# EK-TM4C1294XL_REV_D.net
KiCad netlist of a schematic drawn in EAGLE
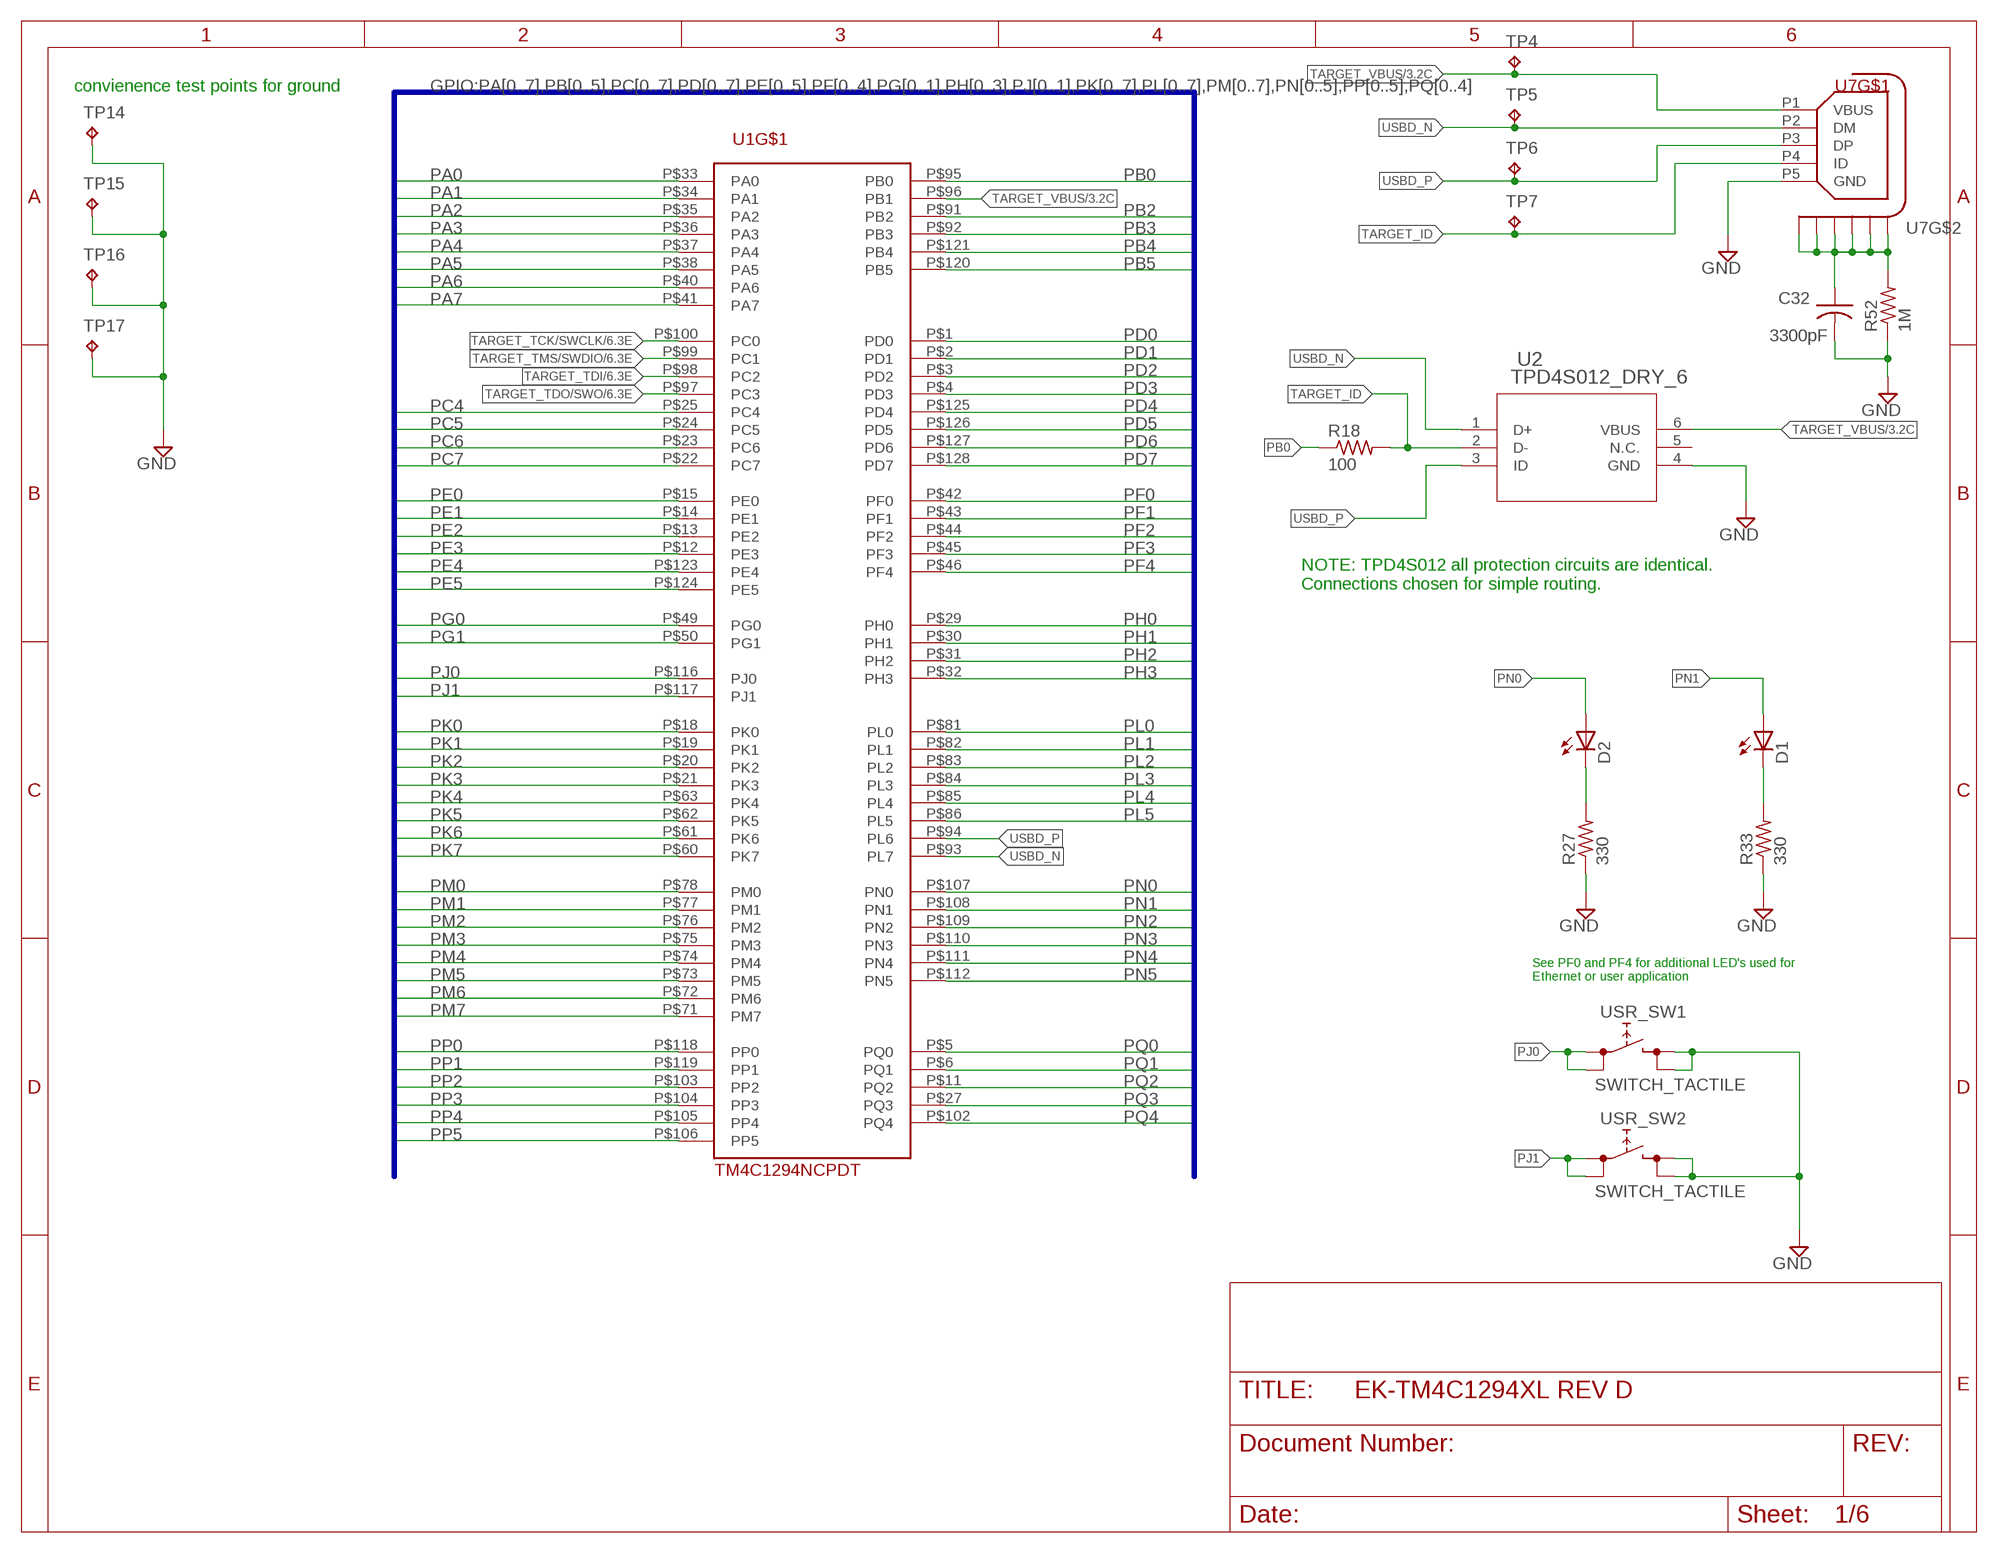
[diagram p0: schematic, sheet 1]
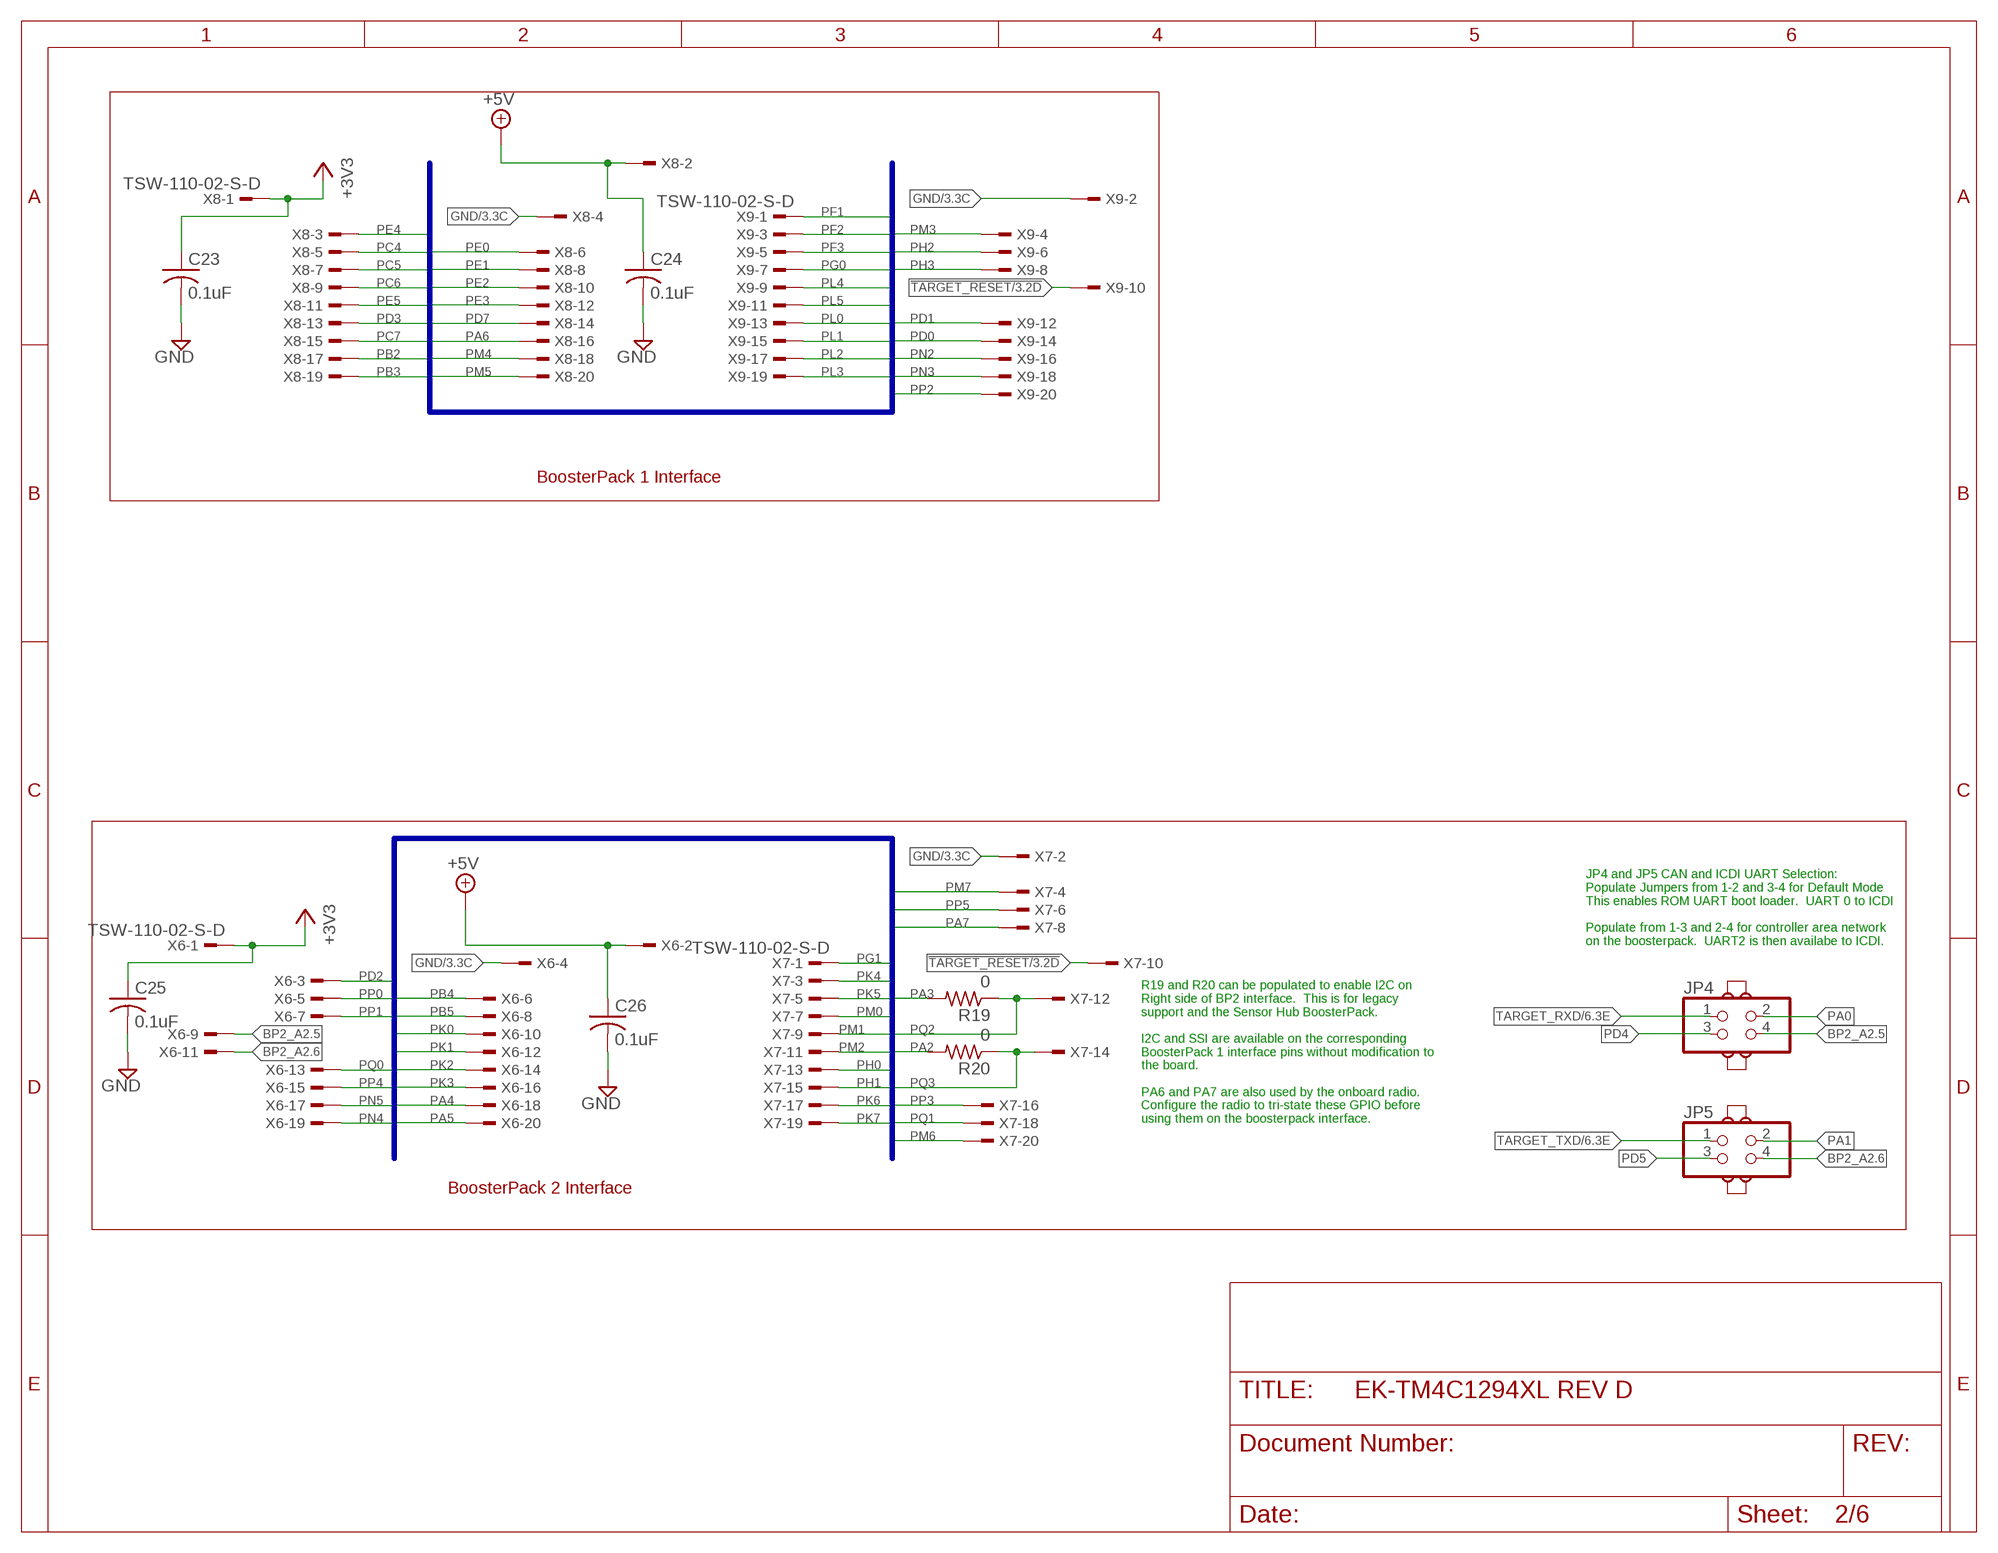
[diagram p1: schematic, sheet 2]
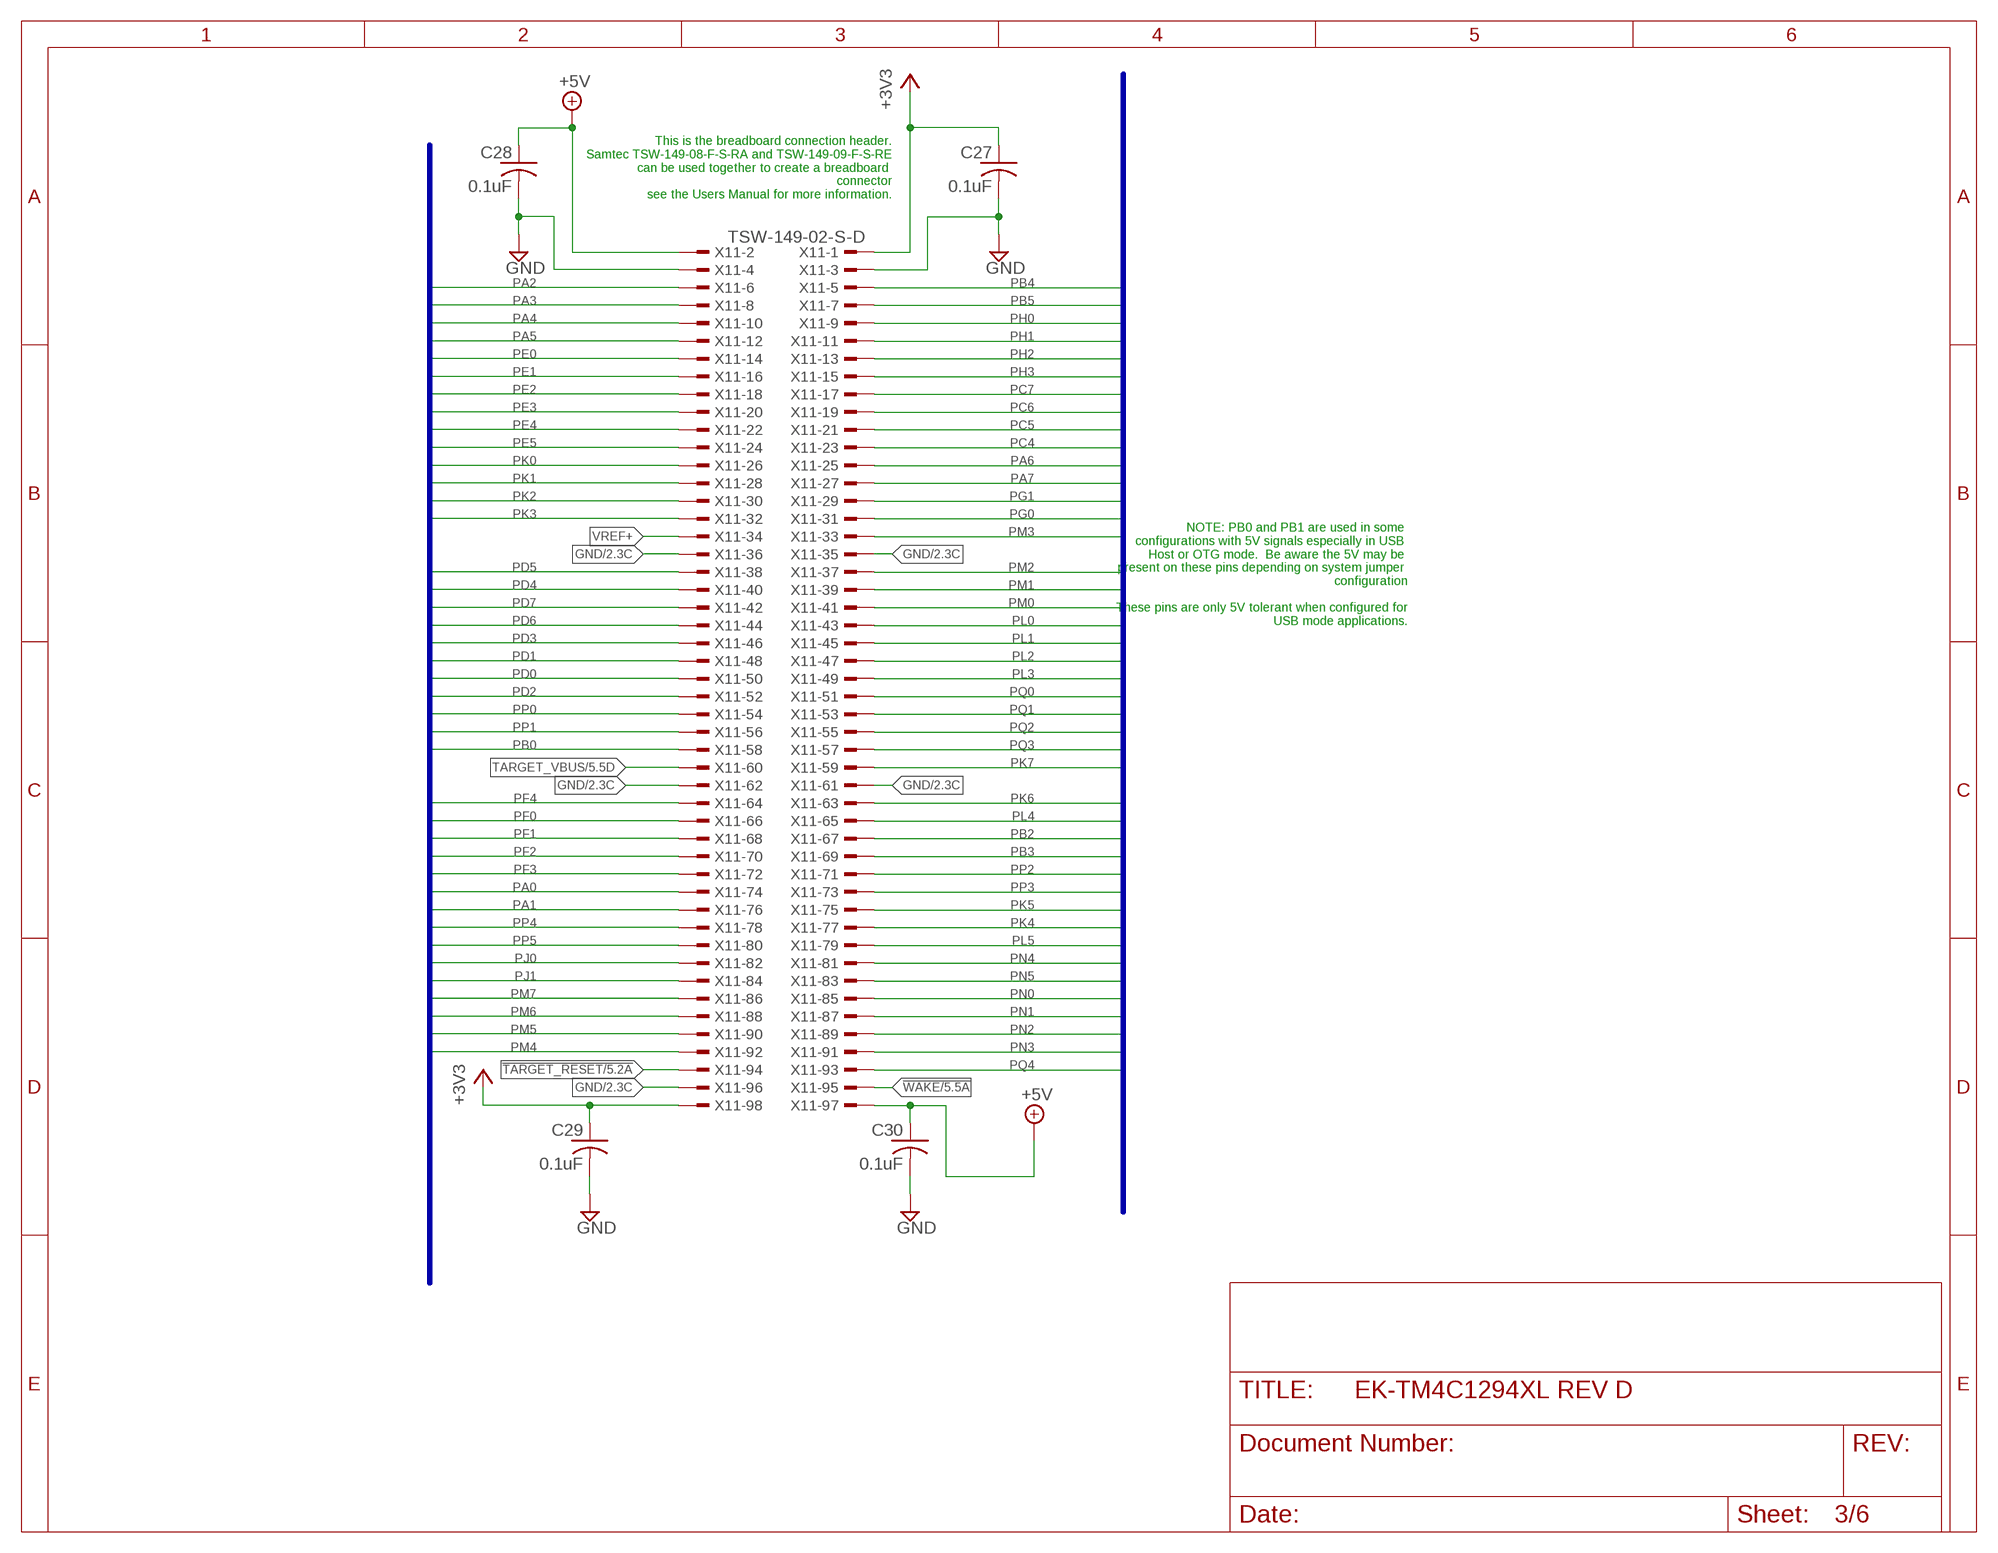
[diagram p2: schematic, sheet 3]
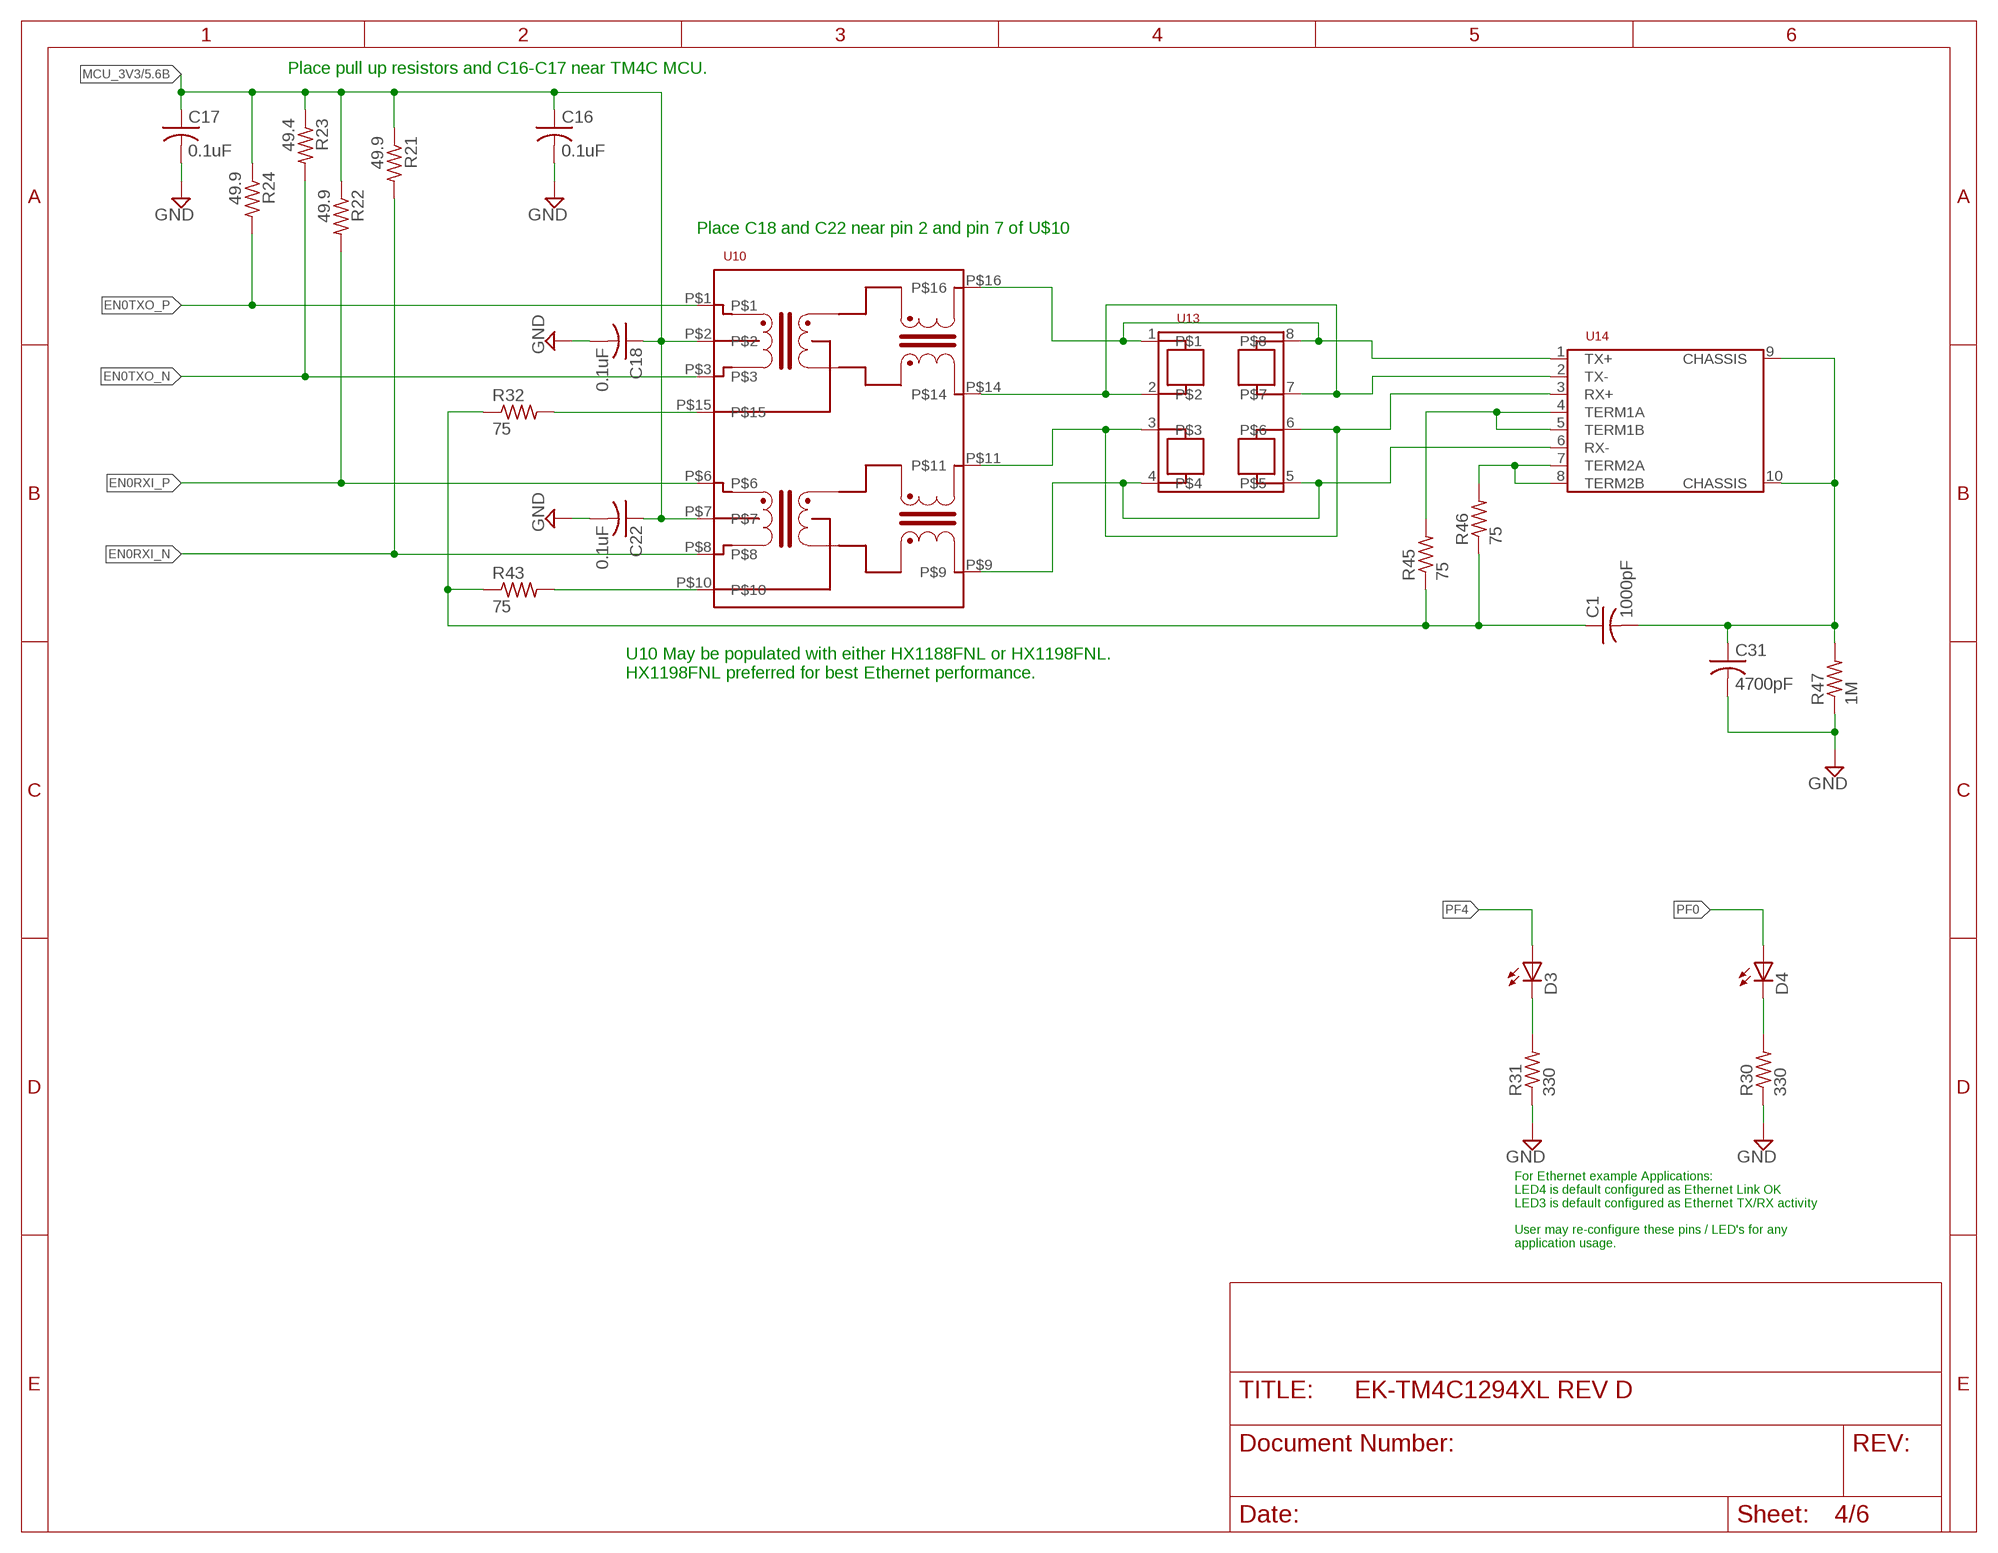
[diagram p3: schematic, sheet 4]
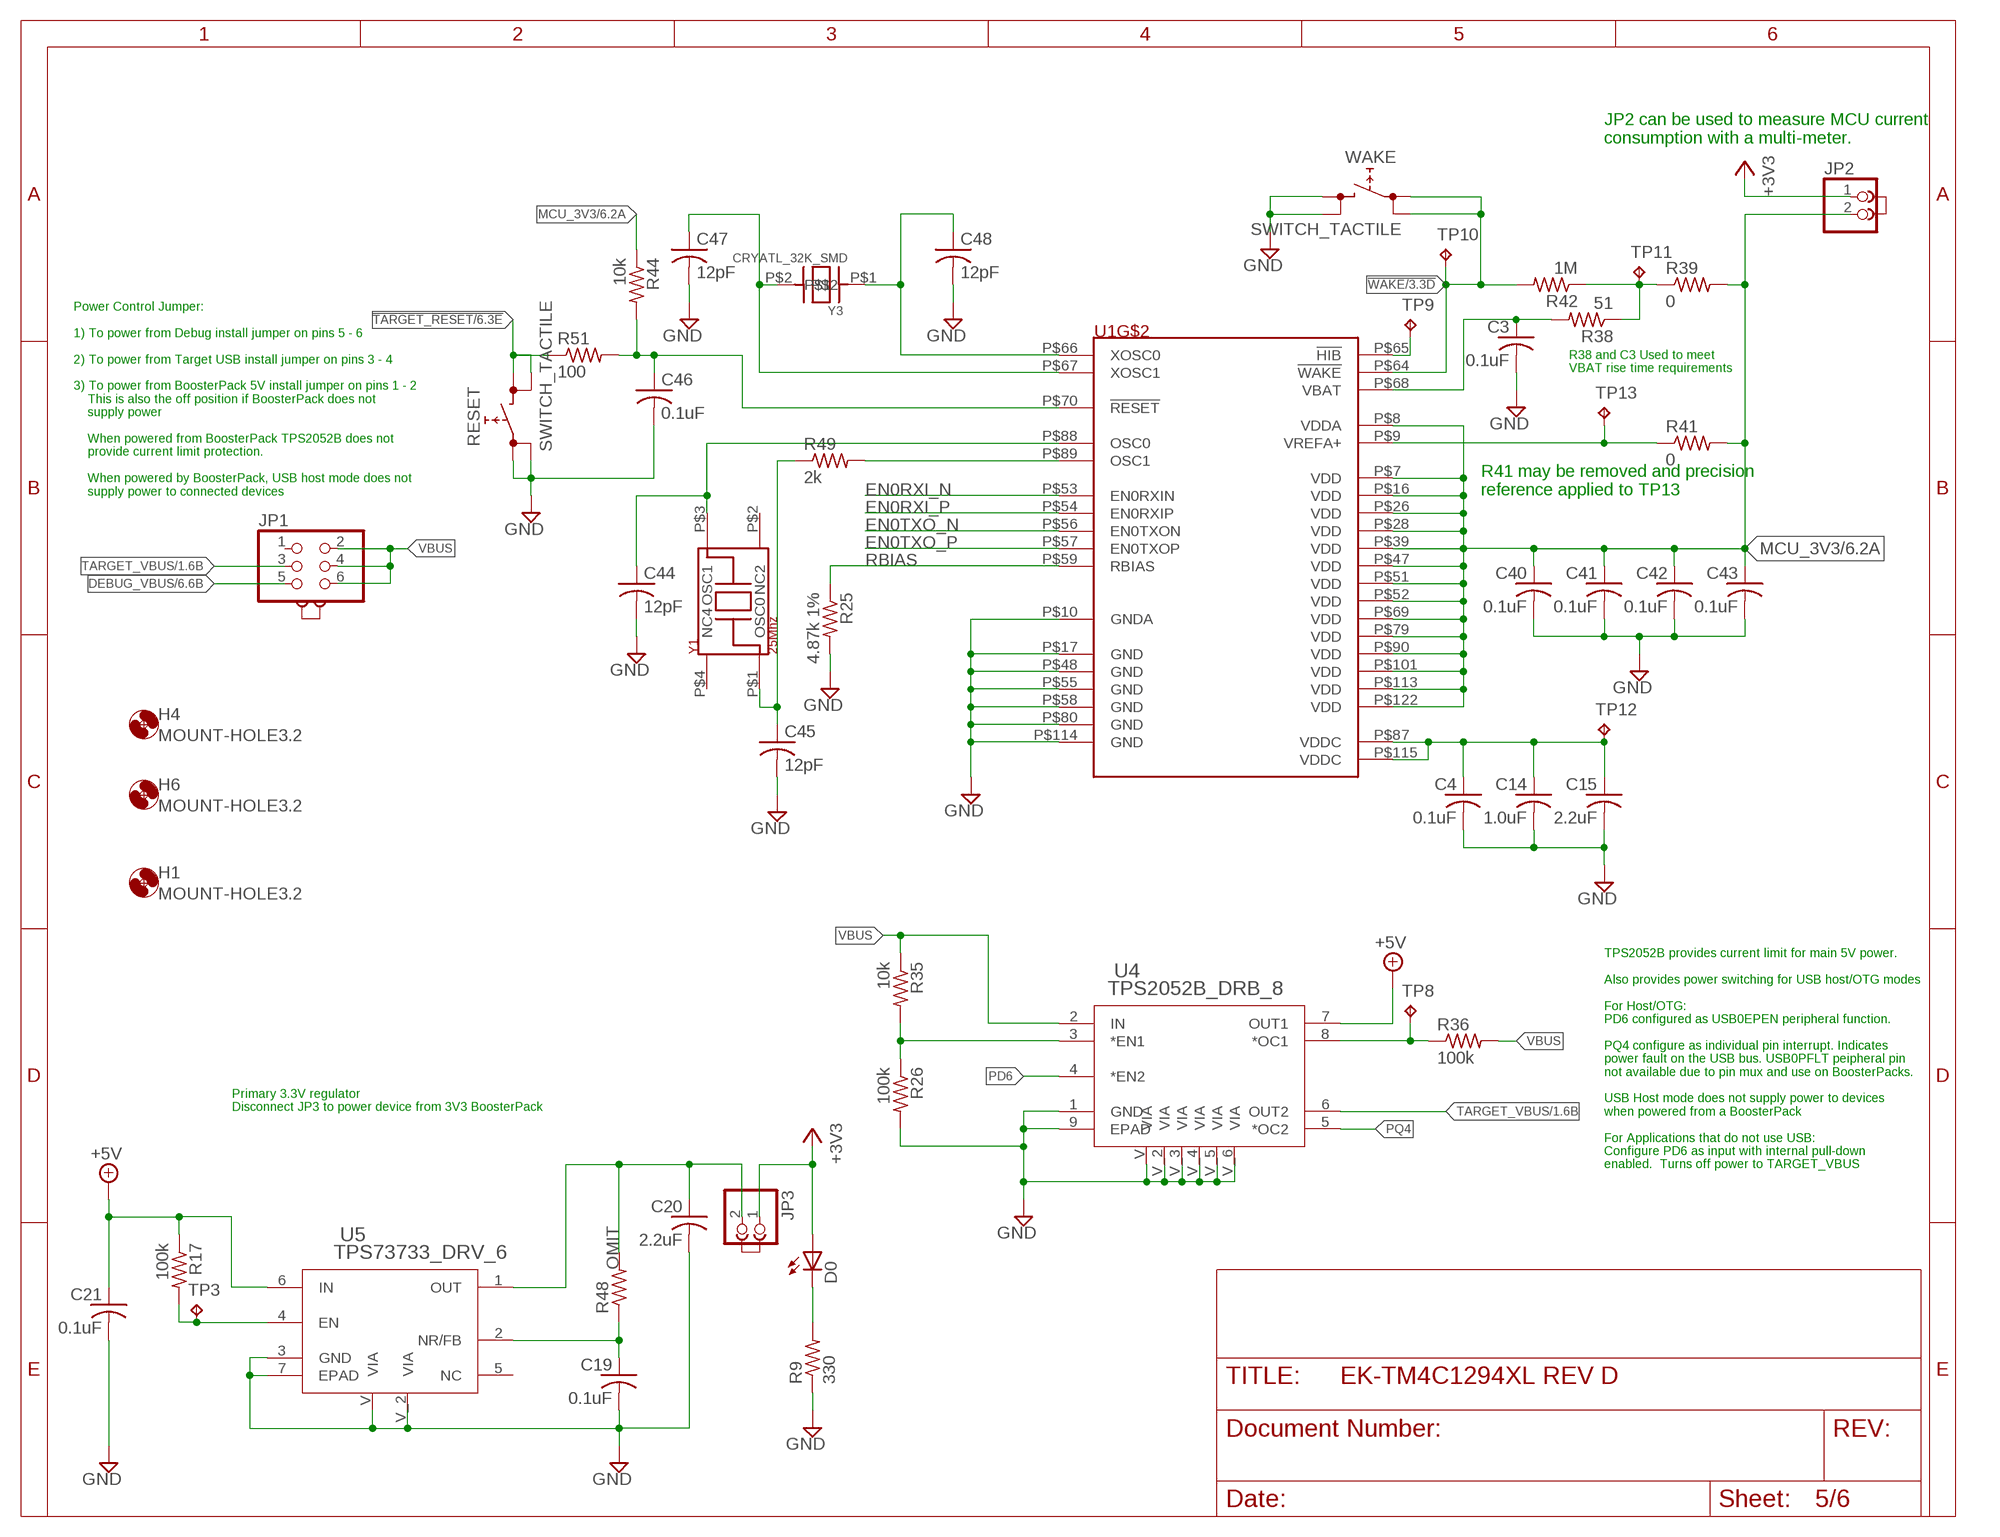
[diagram p4: schematic, sheet 5]
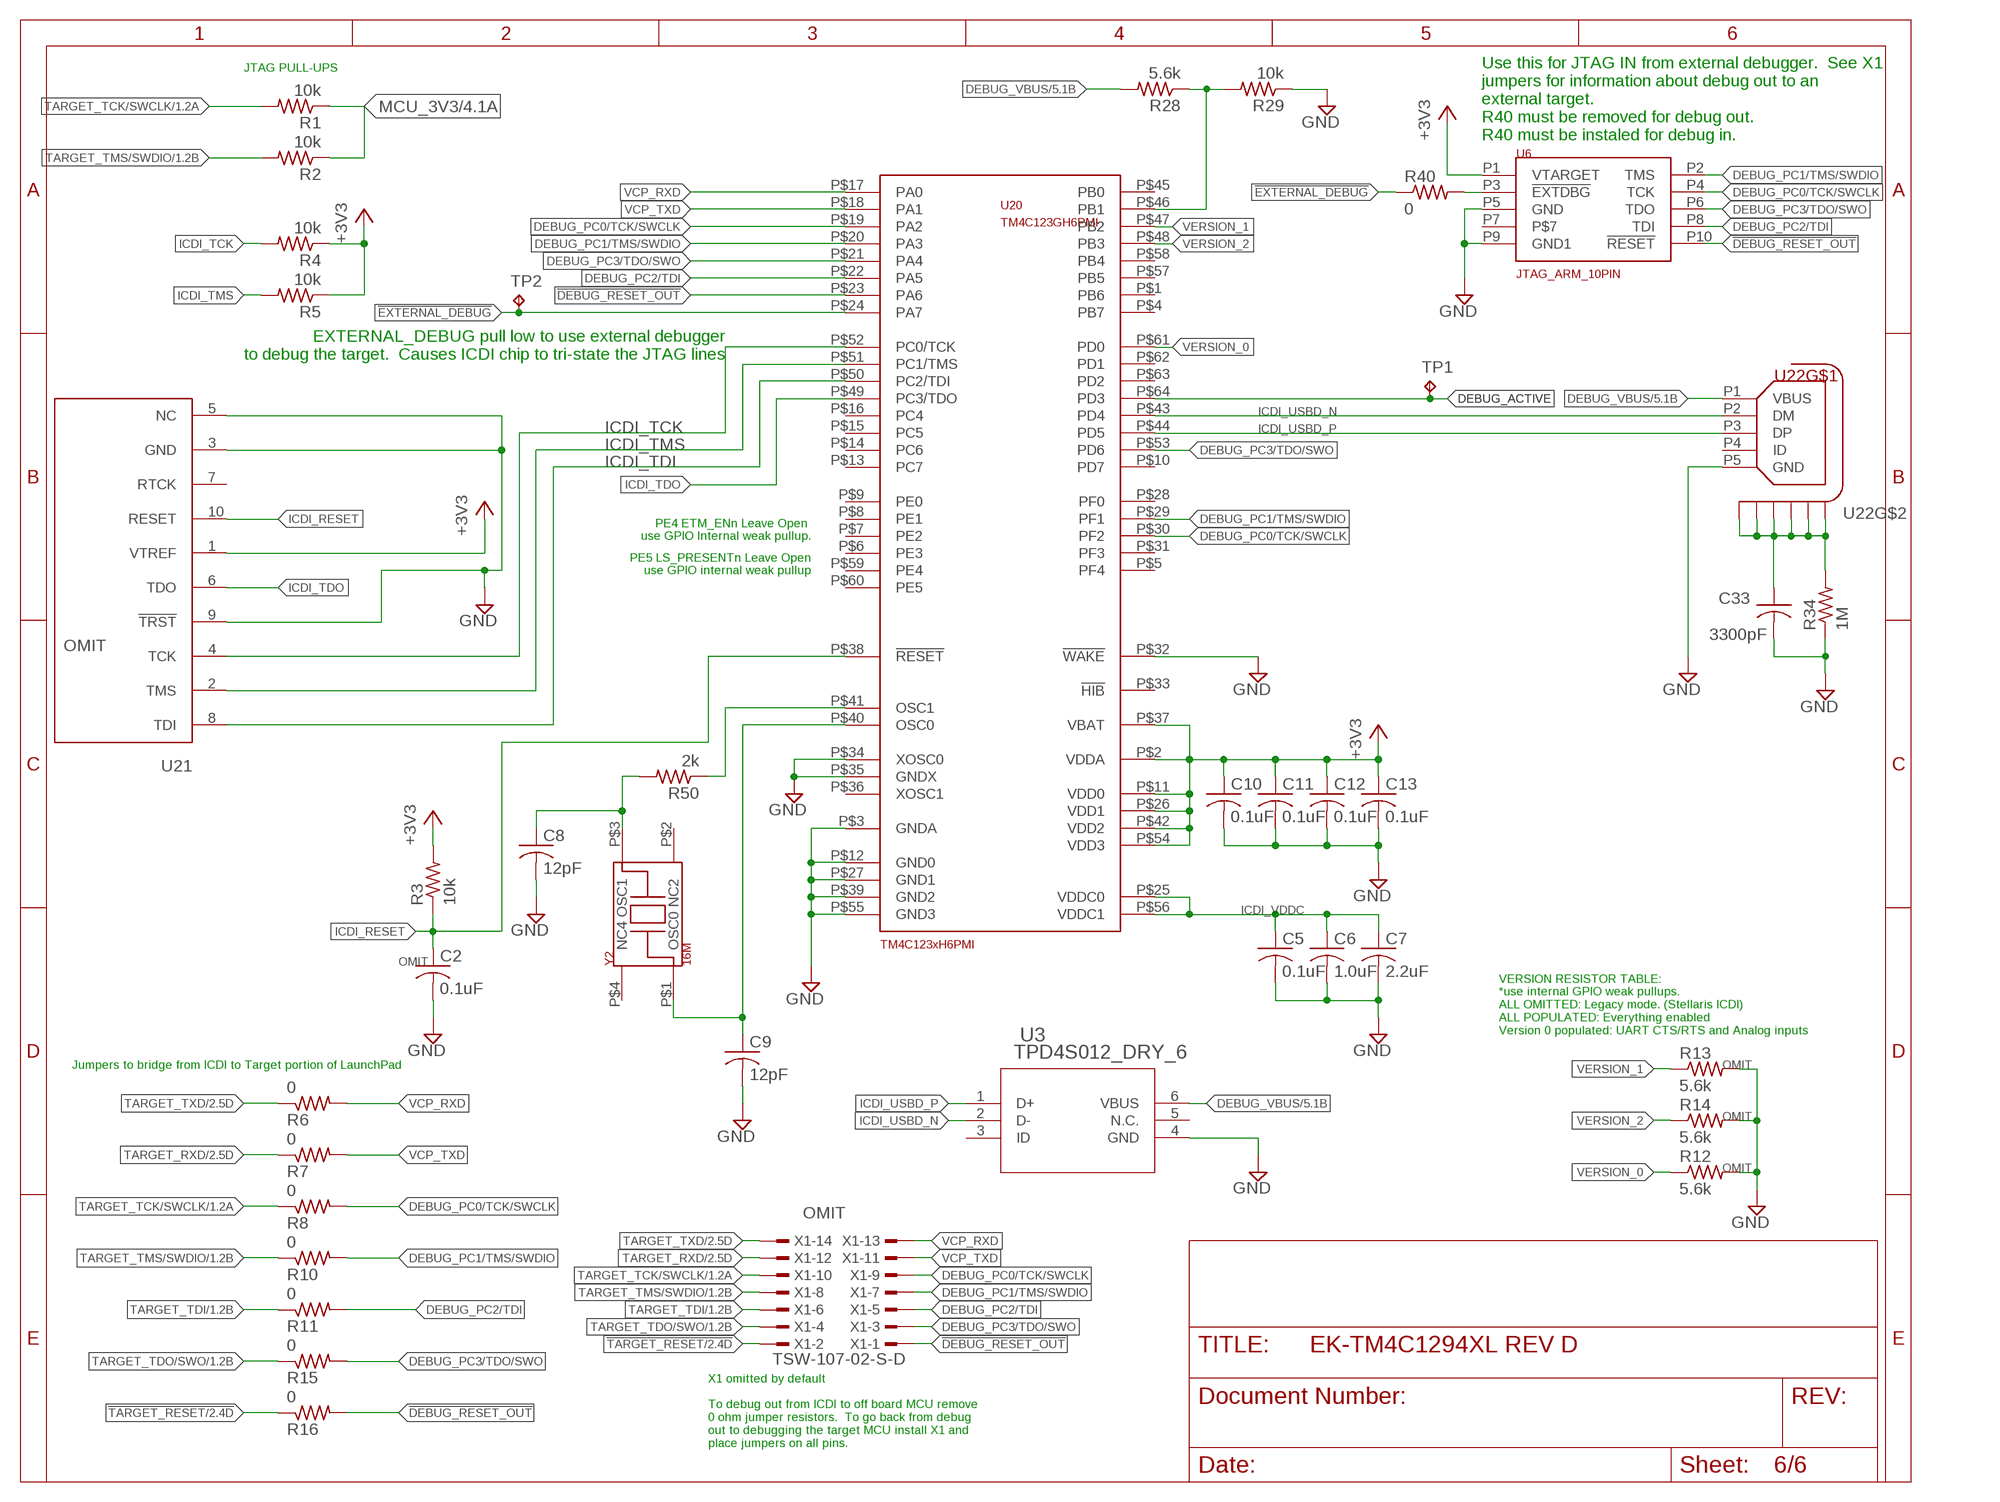
[diagram p5: schematic, sheet 6]

(export (version "E")
  (design (tool "Eeschema 10.0.6"))
  (components
    (comp (ref "C2")
      (value "0.1uF")
      (footprint "eagle-import:C0402")
      (fields (field (name "POPOP") "OMIT"))
      (libsource (lib "eagle-import") (part "ek-tm4c129exl_C-USC0402"))
    )
    (comp (ref "C5")
      (value "0.1uF")
      (footprint "eagle-import:C0402")
      (libsource (lib "eagle-import") (part "ek-tm4c129exl_C-USC0402"))
    )
    (comp (ref "C6")
      (value "1.0uF")
      (footprint "eagle-import:C0402")
      (libsource (lib "eagle-import") (part "ek-tm4c129exl_C-USC0402"))
    )
    (comp (ref "C7")
      (value "2.2uF")
      (footprint "eagle-import:C0603")
      (libsource (lib "eagle-import") (part "ek-tm4c129exl_C-USC0603"))
    )
    (comp (ref "C8")
      (value "12pF")
      (footprint "eagle-import:C0402")
      (libsource (lib "eagle-import") (part "ek-tm4c129exl_C-USC0402"))
    )
    (comp (ref "C9")
      (value "12pF")
      (footprint "eagle-import:C0402")
      (libsource (lib "eagle-import") (part "ek-tm4c129exl_C-USC0402"))
    )
    (comp (ref "C10")
      (value "0.1uF")
      (footprint "eagle-import:C0402")
      (libsource (lib "eagle-import") (part "ek-tm4c129exl_C-USC0402"))
    )
    (comp (ref "C11")
      (value "0.1uF")
      (footprint "eagle-import:C0402")
      (libsource (lib "eagle-import") (part "ek-tm4c129exl_C-USC0402"))
    )
    (comp (ref "C12")
      (value "0.1uF")
      (footprint "eagle-import:C0402")
      (libsource (lib "eagle-import") (part "ek-tm4c129exl_C-USC0402"))
    )
    (comp (ref "C13")
      (value "0.1uF")
      (footprint "eagle-import:C0402")
      (libsource (lib "eagle-import") (part "ek-tm4c129exl_C-USC0402"))
    )
    (comp (ref "C33")
      (value "3300pF")
      (footprint "eagle-import:C0603")
      (libsource (lib "eagle-import") (part "C-USC0603"))
    )
    (comp (ref "R1")
      (value "10k")
      (footprint "eagle-import:R0402")
      (libsource (lib "eagle-import") (part "ek-tm4c129exl_R-US_R0402"))
    )
    (comp (ref "R2")
      (value "10k")
      (footprint "eagle-import:R0402")
      (libsource (lib "eagle-import") (part "ek-tm4c129exl_R-US_R0402"))
    )
    (comp (ref "R3")
      (value "10k")
      (footprint "eagle-import:R0402")
      (libsource (lib "eagle-import") (part "ek-tm4c129exl_R-US_R0402"))
    )
    (comp (ref "R4")
      (value "10k")
      (footprint "eagle-import:R0402")
      (libsource (lib "eagle-import") (part "ek-tm4c129exl_R-US_R0402"))
    )
    (comp (ref "R5")
      (value "10k")
      (footprint "eagle-import:R0402")
      (libsource (lib "eagle-import") (part "ek-tm4c129exl_R-US_R0402"))
    )
    (comp (ref "R6")
      (value "0")
      (footprint "eagle-import:R0402")
      (libsource (lib "eagle-import") (part "ek-tm4c129exl_R-US_R0402"))
    )
    (comp (ref "R7")
      (value "0")
      (footprint "eagle-import:R0402")
      (libsource (lib "eagle-import") (part "ek-tm4c129exl_R-US_R0402"))
    )
    (comp (ref "R8")
      (value "0")
      (footprint "eagle-import:R0402")
      (libsource (lib "eagle-import") (part "ek-tm4c129exl_R-US_R0402"))
    )
    (comp (ref "R10")
      (value "0")
      (footprint "eagle-import:R0402")
      (libsource (lib "eagle-import") (part "ek-tm4c129exl_R-US_R0402"))
    )
    (comp (ref "R11")
      (value "0")
      (footprint "eagle-import:R0402")
      (libsource (lib "eagle-import") (part "ek-tm4c129exl_R-US_R0402"))
    )
    (comp (ref "R12")
      (value "5.6k")
      (footprint "eagle-import:R0402")
      (fields (field (name "POPOP") "OMIT"))
      (libsource (lib "eagle-import") (part "ek-tm4c129exl_R-US_R0402"))
    )
    (comp (ref "R13")
      (value "5.6k")
      (footprint "eagle-import:R0402")
      (fields (field (name "POPOP") "OMIT"))
      (libsource (lib "eagle-import") (part "ek-tm4c129exl_R-US_R0402"))
    )
    (comp (ref "R14")
      (value "5.6k")
      (footprint "eagle-import:R0402")
      (fields (field (name "POPOP") "OMIT"))
      (libsource (lib "eagle-import") (part "ek-tm4c129exl_R-US_R0402"))
    )
    (comp (ref "R15")
      (value "0")
      (footprint "eagle-import:R0402")
      (libsource (lib "eagle-import") (part "ek-tm4c129exl_R-US_R0402"))
    )
    (comp (ref "R16")
      (value "0")
      (footprint "eagle-import:R0402")
      (libsource (lib "eagle-import") (part "ek-tm4c129exl_R-US_R0402"))
    )
    (comp (ref "R28")
      (value "5.6k")
      (footprint "eagle-import:R0402")
      (libsource (lib "eagle-import") (part "ek-tm4c129exl_R-US_R0402"))
    )
    (comp (ref "R29")
      (value "10k")
      (footprint "eagle-import:R0402")
      (libsource (lib "eagle-import") (part "ek-tm4c129exl_R-US_R0402"))
    )
    (comp (ref "R34")
      (value "1M")
      (footprint "eagle-import:R0603")
      (libsource (lib "eagle-import") (part "R-US_R0603"))
    )
    (comp (ref "R40")
      (value "0")
      (footprint "eagle-import:R0402")
      (libsource (lib "eagle-import") (part "ek-tm4c129exl_R-US_R0402"))
    )
    (comp (ref "R50")
      (value "2k")
      (footprint "eagle-import:R0402")
      (libsource (lib "eagle-import") (part "ek-tm4c129exl_R-US_R0402"))
    )
    (comp (ref "TP1")
      (value "TPPAD1-13")
      (footprint "eagle-import:P1-13")
      (libsource (lib "eagle-import") (part "TPPAD1-13"))
    )
    (comp (ref "TP2")
      (value "TPPAD1-13")
      (footprint "eagle-import:P1-13")
      (libsource (lib "eagle-import") (part "TPPAD1-13"))
    )
    (comp (ref "U3")
      (value "TPD4S012_DRY_6")
      (footprint "eagle-import:DRY6")
      (fields
        (field (name "GENERIC_PART_NUMBER") "TPD4S012")
        (field (name "MANUFACTURER") "Texas Instruments")
        (field (name "MANUFACTURER_PART_NUMBER") "tpd4s012_dry_6")
      )
      (libsource (lib "eagle-import") (part "TPD4S012_DRY_6"))
    )
    (comp (ref "U6")
      (value "JTAG_ARM_10PIN")
      (footprint "eagle-import:CON_2X5_50MIL")
      (libsource (lib "eagle-import") (part "JTAG_ARM_10PIN"))
    )
    (comp (ref "U20")
      (value "TM4C123GH6PMI")
      (footprint "eagle-import:LQFP-64-PM")
      (libsource (lib "eagle-import") (part "TM4C123GH6PMI"))
    )
    (comp (ref "U21")
      (value "TC2050-NL-MCP-NL")
      (footprint "eagle-import:TC2030-MCP-NL")
      (fields (field (name "POPOP") "OMIT"))
      (libsource (lib "eagle-import") (part "TC2050-NL-MCP-NL"))
    )
    (comp (ref "U22")
      (value "CON_USB_FCI_MICRO_B_10118194")
      (footprint "eagle-import:CON_USB_MICRO_B_FCI_10118194")
      (fields (field (name "GNUM") "G20-USBU-THB-CEB"))
      (libsource (lib "eagle-import") (part "CON_USB_FCI_MICRO_B_10118194"))
    )
    (comp (ref "X1")
      (value "TSW-107-02-S-D")
      (footprint "eagle-import:TSW-107-02-S-D")
      (fields (field (name "GNUM") "G22-THVEU-2X7P-BAB") (field (name "POPOP") "OMIT"))
      (libsource (lib "eagle-import") (part "TSW-107-02-S-D"))
    )
    (comp (ref "Y2")
      (value "16M")
      (footprint "eagle-import:NDK3.2X2.5")
      (libsource (lib "eagle-import") (part "NX3225GA"))
    )
    (comp (ref "C32")
      (value "3300pF")
      (footprint "eagle-import:C0603")
      (libsource (lib "eagle-import") (part "C-USC0603"))
    )
    (comp (ref "D1")
      (value "LEDCHIPLED_0603")
      (footprint "eagle-import:CHIPLED_0603")
      (libsource (lib "eagle-import") (part "LEDCHIPLED_0603"))
    )
    (comp (ref "D2")
      (value "LEDCHIPLED_0603")
      (footprint "eagle-import:CHIPLED_0603")
      (libsource (lib "eagle-import") (part "LEDCHIPLED_0603"))
    )
    (comp (ref "R18")
      (value "100")
      (footprint "eagle-import:R0402")
      (libsource (lib "eagle-import") (part "ek-tm4c129exl_R-US_R0402"))
    )
    (comp (ref "R27")
      (value "330")
      (footprint "eagle-import:R0402")
      (libsource (lib "eagle-import") (part "ek-tm4c129exl_R-US_R0402"))
    )
    (comp (ref "R33")
      (value "330")
      (footprint "eagle-import:R0402")
      (libsource (lib "eagle-import") (part "ek-tm4c129exl_R-US_R0402"))
    )
    (comp (ref "R52")
      (value "1M")
      (footprint "eagle-import:R0603")
      (libsource (lib "eagle-import") (part "R-US_R0603"))
    )
    (comp (ref "TP4")
      (value "TPPAD1-13")
      (footprint "eagle-import:P1-13")
      (libsource (lib "eagle-import") (part "TPPAD1-13"))
    )
    (comp (ref "TP5")
      (value "TPPAD1-13")
      (footprint "eagle-import:P1-13")
      (libsource (lib "eagle-import") (part "TPPAD1-13"))
    )
    (comp (ref "TP6")
      (value "TPPAD1-13")
      (footprint "eagle-import:P1-13")
      (libsource (lib "eagle-import") (part "TPPAD1-13"))
    )
    (comp (ref "TP7")
      (value "TPPAD1-13")
      (footprint "eagle-import:P1-13")
      (libsource (lib "eagle-import") (part "TPPAD1-13"))
    )
    (comp (ref "TP14")
      (value "TPPAD1-13")
      (footprint "eagle-import:P1-13")
      (libsource (lib "eagle-import") (part "TPPAD1-13"))
    )
    (comp (ref "TP15")
      (value "TPPAD1-13")
      (footprint "eagle-import:P1-13")
      (libsource (lib "eagle-import") (part "TPPAD1-13"))
    )
    (comp (ref "TP16")
      (value "TPPAD1-13")
      (footprint "eagle-import:P1-13")
      (libsource (lib "eagle-import") (part "TPPAD1-13"))
    )
    (comp (ref "TP17")
      (value "TPPAD1-13")
      (footprint "eagle-import:P1-13")
      (libsource (lib "eagle-import") (part "TPPAD1-13"))
    )
    (comp (ref "U1")
      (value "TM4C1294NCPDT")
      (footprint "eagle-import:TQFP-128")
      (fields (field (name "GNUM") "G50-QF128-C1294-ALH"))
      (libsource (lib "eagle-import") (part "TM4C1294NCPDT"))
    )
    (comp (ref "U2")
      (value "TPD4S012_DRY_6")
      (footprint "eagle-import:DRY6")
      (fields
        (field (name "GENERIC_PART_NUMBER") "TPD4S012")
        (field (name "MANUFACTURER") "Texas Instruments")
        (field (name "MANUFACTURER_PART_NUMBER") "tpd4s012_dry_6")
      )
      (libsource (lib "eagle-import") (part "TPD4S012_DRY_6"))
    )
    (comp (ref "U7")
      (value "CON_USB_HIROSE_MICRO_AB_ZX62D_AB_5P8")
      (footprint "eagle-import:CON_USB_MICRO_AB_HIROSE_ZX62D-AB-5P8")
      (fields (field (name "GNUM") "G20-USBU-THAB-CEB"))
      (libsource (lib "eagle-import") (part "CON_USB_HIROSE_MICRO_AB_ZX62D_AB_5P8"))
    )
    (comp (ref "USR_SW1")
      (value "SWITCH_TACTILE")
      (footprint "eagle-import:SWITCH_6MM_6MM_TE_CON_SMD")
      (libsource (lib "eagle-import") (part "SWITCH_TACTILE"))
    )
    (comp (ref "USR_SW2")
      (value "SWITCH_TACTILE")
      (footprint "eagle-import:SWITCH_6MM_6MM_TE_CON_SMD")
      (libsource (lib "eagle-import") (part "SWITCH_TACTILE"))
    )
    (comp (ref "C3")
      (value "0.1uF")
      (footprint "eagle-import:C0402")
      (libsource (lib "eagle-import") (part "ek-tm4c129exl_C-USC0402"))
    )
    (comp (ref "C4")
      (value "0.1uF")
      (footprint "eagle-import:C0402")
      (libsource (lib "eagle-import") (part "ek-tm4c129exl_C-USC0402"))
    )
    (comp (ref "C14")
      (value "1.0uF")
      (footprint "eagle-import:C0402")
      (libsource (lib "eagle-import") (part "ek-tm4c129exl_C-USC0402"))
    )
    (comp (ref "C15")
      (value "2.2uF")
      (footprint "eagle-import:C0603K")
      (fields (field (name "DIGIKEY_PARTNUM") "311-1451-2-ND"))
      (libsource (lib "eagle-import") (part "ek-tm4c129exl_C-USC0603K"))
    )
    (comp (ref "C19")
      (value "0.1uF")
      (footprint "eagle-import:C0402")
      (libsource (lib "eagle-import") (part "ek-tm4c129exl_C-USC0402"))
    )
    (comp (ref "C20")
      (value "2.2uF")
      (footprint "eagle-import:C0603K")
      (fields (field (name "DIGIKEY_PARTNUM") "311-1451-2-ND"))
      (libsource (lib "eagle-import") (part "ek-tm4c129exl_C-USC0603K"))
    )
    (comp (ref "C21")
      (value "0.1uF")
      (footprint "eagle-import:C0402")
      (libsource (lib "eagle-import") (part "ek-tm4c129exl_C-USC0402"))
    )
    (comp (ref "C40")
      (value "0.1uF")
      (footprint "eagle-import:C0402")
      (libsource (lib "eagle-import") (part "ek-tm4c129exl_C-USC0402"))
    )
    (comp (ref "C41")
      (value "0.1uF")
      (footprint "eagle-import:C0402")
      (libsource (lib "eagle-import") (part "ek-tm4c129exl_C-USC0402"))
    )
    (comp (ref "C42")
      (value "0.1uF")
      (footprint "eagle-import:C0402")
      (libsource (lib "eagle-import") (part "ek-tm4c129exl_C-USC0402"))
    )
    (comp (ref "C43")
      (value "0.1uF")
      (footprint "eagle-import:C0402")
      (libsource (lib "eagle-import") (part "ek-tm4c129exl_C-USC0402"))
    )
    (comp (ref "C44")
      (value "12pF")
      (footprint "eagle-import:C0402")
      (libsource (lib "eagle-import") (part "ek-tm4c129exl_C-USC0402"))
    )
    (comp (ref "C45")
      (value "12pF")
      (footprint "eagle-import:C0402")
      (libsource (lib "eagle-import") (part "ek-tm4c129exl_C-USC0402"))
    )
    (comp (ref "C46")
      (value "0.1uF")
      (footprint "eagle-import:C0402")
      (libsource (lib "eagle-import") (part "ek-tm4c129exl_C-USC0402"))
    )
    (comp (ref "C47")
      (value "12pF")
      (footprint "eagle-import:C0402")
      (libsource (lib "eagle-import") (part "ek-tm4c129exl_C-USC0402"))
    )
    (comp (ref "C48")
      (value "12pF")
      (footprint "eagle-import:C0402")
      (libsource (lib "eagle-import") (part "ek-tm4c129exl_C-USC0402"))
    )
    (comp (ref "D0")
      (value "LEDCHIPLED_0603")
      (footprint "eagle-import:CHIPLED_0603")
      (libsource (lib "eagle-import") (part "LEDCHIPLED_0603"))
    )
    (comp (ref "H1")
      (value "MOUNT-HOLE3.2")
      (footprint "eagle-import:3,2")
      (libsource (lib "eagle-import") (part "MOUNT-HOLE3.2"))
    )
    (comp (ref "H4")
      (value "MOUNT-HOLE3.2")
      (footprint "eagle-import:3,2")
      (libsource (lib "eagle-import") (part "MOUNT-HOLE3.2"))
    )
    (comp (ref "H6")
      (value "MOUNT-HOLE3.2")
      (footprint "eagle-import:3,2")
      (libsource (lib "eagle-import") (part "MOUNT-HOLE3.2"))
    )
    (comp (ref "J1")
      (value "JUMPER")
      (footprint "eagle-import:JUMP")
      (libsource (lib "eagle-import") (part "JUMPER"))
    )
    (comp (ref "J2")
      (value "JUMPER")
      (footprint "eagle-import:JUMP")
      (libsource (lib "eagle-import") (part "JUMPER"))
    )
    (comp (ref "J3")
      (value "JUMPER")
      (footprint "eagle-import:JUMP")
      (libsource (lib "eagle-import") (part "JUMPER"))
    )
    (comp (ref "JP1")
      (value "PINHD-2X3")
      (footprint "eagle-import:2X03")
      (libsource (lib "eagle-import") (part "PINHD-2X3"))
    )
    (comp (ref "JP2")
      (value "PINHD-1X2")
      (footprint "eagle-import:1X02")
      (libsource (lib "eagle-import") (part "PINHD-1X2"))
    )
    (comp (ref "JP3")
      (value "PINHD-1X2")
      (footprint "eagle-import:1X02")
      (libsource (lib "eagle-import") (part "PINHD-1X2"))
    )
    (comp (ref "R9")
      (value "330")
      (footprint "eagle-import:R0402")
      (libsource (lib "eagle-import") (part "ek-tm4c129exl_R-US_R0402"))
    )
    (comp (ref "R17")
      (value "100k")
      (footprint "eagle-import:R0402")
      (libsource (lib "eagle-import") (part "ek-tm4c129exl_R-US_R0402"))
    )
    (comp (ref "R25")
      (value "4.87k 1%")
      (footprint "eagle-import:R0402")
      (libsource (lib "eagle-import") (part "ek-tm4c129exl_R-US_R0402"))
    )
    (comp (ref "R26")
      (value "100k")
      (footprint "eagle-import:R0402")
      (libsource (lib "eagle-import") (part "ek-tm4c129exl_R-US_R0402"))
    )
    (comp (ref "R35")
      (value "10k")
      (footprint "eagle-import:R0402")
      (libsource (lib "eagle-import") (part "ek-tm4c129exl_R-US_R0402"))
    )
    (comp (ref "R36")
      (value "100k")
      (footprint "eagle-import:R0402")
      (libsource (lib "eagle-import") (part "ek-tm4c129exl_R-US_R0402"))
    )
    (comp (ref "R38")
      (value "51")
      (footprint "eagle-import:R0402")
      (libsource (lib "eagle-import") (part "ek-tm4c129exl_R-US_R0402"))
    )
    (comp (ref "R39")
      (value "0")
      (footprint "eagle-import:R0402")
      (libsource (lib "eagle-import") (part "ek-tm4c129exl_R-US_R0402"))
    )
    (comp (ref "R41")
      (value "0")
      (footprint "eagle-import:R0402")
      (libsource (lib "eagle-import") (part "ek-tm4c129exl_R-US_R0402"))
    )
    (comp (ref "R42")
      (value "1M")
      (footprint "eagle-import:R0402")
      (libsource (lib "eagle-import") (part "ek-tm4c129exl_R-US_R0402"))
    )
    (comp (ref "R44")
      (value "10k")
      (footprint "eagle-import:R0402")
      (libsource (lib "eagle-import") (part "ek-tm4c129exl_R-US_R0402"))
    )
    (comp (ref "R48")
      (value "R-US_R0402")
      (footprint "eagle-import:R0402")
      (fields (field (name "POPOP") "OMIT"))
      (libsource (lib "eagle-import") (part "ek-tm4c129exl_R-US_R0402"))
    )
    (comp (ref "R49")
      (value "2k")
      (footprint "eagle-import:R0402")
      (libsource (lib "eagle-import") (part "ek-tm4c129exl_R-US_R0402"))
    )
    (comp (ref "R51")
      (value "100")
      (footprint "eagle-import:R0402")
      (libsource (lib "eagle-import") (part "ek-tm4c129exl_R-US_R0402"))
    )
    (comp (ref "RESET")
      (value "SWITCH_TACTILE")
      (footprint "eagle-import:SWITCH_6MM_6MM_TE_CON_SMD")
      (libsource (lib "eagle-import") (part "SWITCH_TACTILE"))
    )
    (comp (ref "TP3")
      (value "TPPAD1-13")
      (footprint "eagle-import:P1-13")
      (libsource (lib "eagle-import") (part "TPPAD1-13"))
    )
    (comp (ref "TP8")
      (value "TPPAD1-13")
      (footprint "eagle-import:P1-13")
      (libsource (lib "eagle-import") (part "TPPAD1-13"))
    )
    (comp (ref "TP9")
      (value "TPPAD1-13")
      (footprint "eagle-import:P1-13")
      (libsource (lib "eagle-import") (part "TPPAD1-13"))
    )
    (comp (ref "TP10")
      (value "TPPAD1-13")
      (footprint "eagle-import:P1-13")
      (libsource (lib "eagle-import") (part "TPPAD1-13"))
    )
    (comp (ref "TP11")
      (value "TPPAD1-13")
      (footprint "eagle-import:P1-13")
      (libsource (lib "eagle-import") (part "TPPAD1-13"))
    )
    (comp (ref "TP12")
      (value "TPPAD1-13")
      (footprint "eagle-import:P1-13")
      (libsource (lib "eagle-import") (part "TPPAD1-13"))
    )
    (comp (ref "TP13")
      (value "TPPAD1-13")
      (footprint "eagle-import:P1-13")
      (libsource (lib "eagle-import") (part "TPPAD1-13"))
    )
    (comp (ref "U4")
      (value "TPS2052B_DRB_8")
      (footprint "eagle-import:DRB8_2P4X1P65")
      (fields
        (field (name "GENERIC_PART_NUMBER") "TPS2052B")
        (field (name "MANUFACTURER") "Texas Instruments")
        (field (name "MANUFACTURER_PART_NUMBER") "tps2052b_drb_8")
      )
      (libsource (lib "eagle-import") (part "TPS2052B_DRB_8"))
    )
    (comp (ref "U5")
      (value "TPS73733_DRV_6")
      (footprint "eagle-import:DRV6_1P6X1")
      (libsource (lib "eagle-import") (part "TPS73733_DRV_6"))
    )
    (comp (ref "WAKE")
      (value "SWITCH_TACTILE")
      (footprint "eagle-import:SWITCH_6MM_6MM_TE_CON_SMD")
      (libsource (lib "eagle-import") (part "SWITCH_TACTILE"))
    )
    (comp (ref "Y1")
      (value "25Mhz")
      (footprint "eagle-import:NDK3.2X2.5")
      (libsource (lib "eagle-import") (part "NX3225GA"))
    )
    (comp (ref "Y3")
      (value "CRYATL_32K_SMD")
      (footprint "eagle-import:CRYSTAL_32K_SMD")
      (libsource (lib "eagle-import") (part "CRYATL_32K_SMD"))
    )
    (comp (ref "C1")
      (value "1000pF")
      (footprint "eagle-import:C1210")
      (libsource (lib "eagle-import") (part "C-USC1210"))
    )
    (comp (ref "C16")
      (value "0.1uF")
      (footprint "eagle-import:C0402")
      (libsource (lib "eagle-import") (part "ek-tm4c129exl_C-USC0402"))
    )
    (comp (ref "C17")
      (value "0.1uF")
      (footprint "eagle-import:C0402")
      (libsource (lib "eagle-import") (part "ek-tm4c129exl_C-USC0402"))
    )
    (comp (ref "C18")
      (value "0.1uF")
      (footprint "eagle-import:C0402")
      (libsource (lib "eagle-import") (part "ek-tm4c129exl_C-USC0402"))
    )
    (comp (ref "C22")
      (value "0.1uF")
      (footprint "eagle-import:C0402")
      (libsource (lib "eagle-import") (part "ek-tm4c129exl_C-USC0402"))
    )
    (comp (ref "C31")
      (value "4700pF")
      (footprint "eagle-import:C1812")
      (libsource (lib "eagle-import") (part "ek-tm4c129exl_C-USC1812"))
    )
    (comp (ref "D3")
      (value "LEDCHIPLED_0603")
      (footprint "eagle-import:CHIPLED_0603")
      (libsource (lib "eagle-import") (part "LEDCHIPLED_0603"))
    )
    (comp (ref "D4")
      (value "LEDCHIPLED_0603")
      (footprint "eagle-import:CHIPLED_0603")
      (libsource (lib "eagle-import") (part "LEDCHIPLED_0603"))
    )
    (comp (ref "R21")
      (value "49.9")
      (footprint "eagle-import:R0402")
      (libsource (lib "eagle-import") (part "ek-tm4c129exl_R-US_R0402"))
    )
    (comp (ref "R22")
      (value "49.9")
      (footprint "eagle-import:R0402")
      (libsource (lib "eagle-import") (part "ek-tm4c129exl_R-US_R0402"))
    )
    (comp (ref "R23")
      (value "49.4")
      (footprint "eagle-import:R0402")
      (libsource (lib "eagle-import") (part "ek-tm4c129exl_R-US_R0402"))
    )
    (comp (ref "R24")
      (value "49.9")
      (footprint "eagle-import:R0402")
      (libsource (lib "eagle-import") (part "ek-tm4c129exl_R-US_R0402"))
    )
    (comp (ref "R30")
      (value "330")
      (footprint "eagle-import:R0402")
      (libsource (lib "eagle-import") (part "ek-tm4c129exl_R-US_R0402"))
    )
    (comp (ref "R31")
      (value "330")
      (footprint "eagle-import:R0402")
      (libsource (lib "eagle-import") (part "ek-tm4c129exl_R-US_R0402"))
    )
    (comp (ref "R32")
      (value "75")
      (footprint "eagle-import:R0402")
      (libsource (lib "eagle-import") (part "ek-tm4c129exl_R-US_R0402"))
    )
    (comp (ref "R43")
      (value "75")
      (footprint "eagle-import:R0402")
      (libsource (lib "eagle-import") (part "ek-tm4c129exl_R-US_R0402"))
    )
    (comp (ref "R45")
      (value "75")
      (footprint "eagle-import:R0402")
      (libsource (lib "eagle-import") (part "ek-tm4c129exl_R-US_R0402"))
    )
    (comp (ref "R46")
      (value "75")
      (footprint "eagle-import:R0402")
      (libsource (lib "eagle-import") (part "ek-tm4c129exl_R-US_R0402"))
    )
    (comp (ref "R47")
      (value "1M")
      (footprint "eagle-import:R1206")
      (libsource (lib "eagle-import") (part "R-US_R1206"))
    )
    (comp (ref "U10")
      (value "MAG_PULSE_HX1188FNL")
      (footprint "eagle-import:MAG_PULSE_HX1188FNL")
      (libsource (lib "eagle-import") (part "MAG_PULSE_HX1188FNL"))
    )
    (comp (ref "U13")
      (value "SLVU2.8-4")
      (footprint "eagle-import:D8")
      (libsource (lib "eagle-import") (part "SLVU2.8-4"))
    )
    (comp (ref "U14")
      (value "JACK_RJ45_NOMAG_NOLED_TECON")
      (footprint "eagle-import:RJ45_TE_CON_NOMAG_NOLED")
      (libsource (lib "eagle-import") (part "JACK_RJ45_NOMAG_NOLED_TECON"))
    )
    (comp (ref "C23")
      (value "0.1uF")
      (footprint "eagle-import:C0402")
      (libsource (lib "eagle-import") (part "ek-tm4c129exl_C-USC0402"))
    )
    (comp (ref "C24")
      (value "0.1uF")
      (footprint "eagle-import:C0402")
      (libsource (lib "eagle-import") (part "ek-tm4c129exl_C-USC0402"))
    )
    (comp (ref "C25")
      (value "0.1uF")
      (footprint "eagle-import:C0402")
      (libsource (lib "eagle-import") (part "ek-tm4c129exl_C-USC0402"))
    )
    (comp (ref "C26")
      (value "0.1uF")
      (footprint "eagle-import:C0402")
      (libsource (lib "eagle-import") (part "ek-tm4c129exl_C-USC0402"))
    )
    (comp (ref "J4")
      (value "JUMPER")
      (footprint "eagle-import:JUMP")
      (libsource (lib "eagle-import") (part "JUMPER"))
    )
    (comp (ref "J5")
      (value "JUMPER")
      (footprint "eagle-import:JUMP")
      (libsource (lib "eagle-import") (part "JUMPER"))
    )
    (comp (ref "J6")
      (value "JUMPER")
      (footprint "eagle-import:JUMP")
      (libsource (lib "eagle-import") (part "JUMPER"))
    )
    (comp (ref "J7")
      (value "JUMPER")
      (footprint "eagle-import:JUMP")
      (libsource (lib "eagle-import") (part "JUMPER"))
    )
    (comp (ref "JP4")
      (value "PINHD-2X2")
      (footprint "eagle-import:2X02")
      (libsource (lib "eagle-import") (part "PINHD-2X2"))
    )
    (comp (ref "JP5")
      (value "PINHD-2X2")
      (footprint "eagle-import:2X02")
      (libsource (lib "eagle-import") (part "PINHD-2X2"))
    )
    (comp (ref "R19")
      (value "0")
      (footprint "eagle-import:R0402")
      (libsource (lib "eagle-import") (part "ek-tm4c129exl_R-US_R0402"))
    )
    (comp (ref "R20")
      (value "0")
      (footprint "eagle-import:R0402")
      (libsource (lib "eagle-import") (part "ek-tm4c129exl_R-US_R0402"))
    )
    (comp (ref "X6")
      (value "TSW-110-02-S-D")
      (footprint "eagle-import:TSW-110-02-S-D")
      (fields (field (name "GNUM") "G22-THSTK-2X10-BAC"))
      (libsource (lib "eagle-import") (part "TSW-110-02-S-D"))
    )
    (comp (ref "X7")
      (value "TSW-110-02-S-D")
      (footprint "eagle-import:TSW-110-02-S-D")
      (fields (field (name "GNUM") "G22-THSTK-2X10-BAC"))
      (libsource (lib "eagle-import") (part "TSW-110-02-S-D"))
    )
    (comp (ref "X8")
      (value "TSW-110-02-S-D")
      (footprint "eagle-import:TSW-110-02-S-D")
      (fields (field (name "GNUM") "G22-THSTK-2X10-BAC"))
      (libsource (lib "eagle-import") (part "TSW-110-02-S-D"))
    )
    (comp (ref "X9")
      (value "TSW-110-02-S-D")
      (footprint "eagle-import:TSW-110-02-S-D")
      (fields (field (name "GNUM") "G22-THSTK-2X10-BAC"))
      (libsource (lib "eagle-import") (part "TSW-110-02-S-D"))
    )
    (comp (ref "C27")
      (value "0.1uF")
      (footprint "eagle-import:C0402")
      (libsource (lib "eagle-import") (part "ek-tm4c129exl_C-USC0402"))
    )
    (comp (ref "C28")
      (value "0.1uF")
      (footprint "eagle-import:C0402")
      (libsource (lib "eagle-import") (part "ek-tm4c129exl_C-USC0402"))
    )
    (comp (ref "C29")
      (value "0.1uF")
      (footprint "eagle-import:C0402")
      (libsource (lib "eagle-import") (part "ek-tm4c129exl_C-USC0402"))
    )
    (comp (ref "C30")
      (value "0.1uF")
      (footprint "eagle-import:C0402")
      (libsource (lib "eagle-import") (part "ek-tm4c129exl_C-USC0402"))
    )
    (comp (ref "X11")
      (value "TSW-149-02-S-D")
      (footprint "eagle-import:TSW-149-02-S-D")
      (fields
        (field (name "GNUM1") "G22-THRE-1x49-AAC")
        (field (name "GNUM2") "G22-THRA-1X49-AAC")
        (field (name "POPOP") "OMIT")
      )
      (libsource (lib "eagle-import") (part "TSW-149-02-S-D"))
    )
  )
  (nets
    (net (code "1") (name "+3V3") (class "Default")
      (node (ref "C10") (pin "1") (pinfunction "1_1") (pintype "passive"))
      (node (ref "C11") (pin "1") (pinfunction "1_1") (pintype "passive"))
      (node (ref "C12") (pin "1") (pinfunction "1_1") (pintype "passive"))
      (node (ref "C13") (pin "1") (pinfunction "1_1") (pintype "passive"))
      (node (ref "C23") (pin "1") (pinfunction "1_1") (pintype "passive"))
      (node (ref "C25") (pin "1") (pinfunction "1_1") (pintype "passive"))
      (node (ref "C27") (pin "1") (pinfunction "1_1") (pintype "passive"))
      (node (ref "C29") (pin "1") (pinfunction "1_1") (pintype "passive"))
      (node (ref "D0") (pin "A") (pinfunction "A_A") (pintype "passive"))
      (node (ref "JP2") (pin "1") (pinfunction "1_1") (pintype "passive"))
      (node (ref "JP3") (pin "1") (pinfunction "1_1") (pintype "passive"))
      (node (ref "R3") (pin "2") (pinfunction "2_2") (pintype "passive"))
      (node (ref "R4") (pin "1") (pinfunction "1_1") (pintype "passive"))
      (node (ref "R5") (pin "1") (pinfunction "1_1") (pintype "passive"))
      (node (ref "U20") (pin "P$11") (pinfunction "VDD0_P$11") (pintype "bidirectional"))
      (node (ref "U20") (pin "P$2") (pinfunction "VDDA_P$2") (pintype "bidirectional"))
      (node (ref "U20") (pin "P$26") (pinfunction "VDD1_P$26") (pintype "bidirectional"))
      (node (ref "U20") (pin "P$37") (pinfunction "VBAT_P$37") (pintype "bidirectional"))
      (node (ref "U20") (pin "P$42") (pinfunction "VDD2_P$42") (pintype "bidirectional"))
      (node (ref "U20") (pin "P$54") (pinfunction "VDD3_P$54") (pintype "bidirectional"))
      (node (ref "U21") (pin "1") (pinfunction "VTREF_1") (pintype "bidirectional"))
      (node (ref "U6") (pin "P1") (pinfunction "VTARGET_P1") (pintype "bidirectional"))
      (node (ref "X11") (pin "1") (pinfunction "1_1") (pintype "passive"))
      (node (ref "X11") (pin "98") (pinfunction "1_98") (pintype "passive"))
      (node (ref "X6") (pin "1") (pinfunction "1_1") (pintype "passive"))
      (node (ref "X8") (pin "1") (pinfunction "1_1") (pintype "passive"))
    )
    (net (code "2") (name "+5V") (class "Default")
      (node (ref "C21") (pin "1") (pinfunction "1_1") (pintype "passive"))
      (node (ref "C24") (pin "1") (pinfunction "1_1") (pintype "passive"))
      (node (ref "C26") (pin "1") (pinfunction "1_1") (pintype "passive"))
      (node (ref "C28") (pin "1") (pinfunction "1_1") (pintype "passive"))
      (node (ref "C30") (pin "1") (pinfunction "1_1") (pintype "passive"))
      (node (ref "R17") (pin "1") (pinfunction "1_1") (pintype "passive"))
      (node (ref "U4") (pin "7") (pinfunction "OUT1_7") (pintype "output"))
      (node (ref "U5") (pin "6") (pinfunction "IN_6") (pintype "input"))
      (node (ref "X11") (pin "2") (pinfunction "1_2") (pintype "passive"))
      (node (ref "X11") (pin "97") (pinfunction "1_97") (pintype "passive"))
      (node (ref "X6") (pin "2") (pinfunction "1_2") (pintype "passive"))
      (node (ref "X8") (pin "2") (pinfunction "1_2") (pintype "passive"))
    )
    (net (code "4") (name "BP2_A2.5") (class "Default")
      (node (ref "JP4") (pin "4") (pinfunction "4_4") (pintype "passive"))
      (node (ref "X6") (pin "9") (pinfunction "1_9") (pintype "passive"))
    )
    (net (code "5") (name "BP2_A2.6") (class "Default")
      (node (ref "JP5") (pin "4") (pinfunction "4_4") (pintype "passive"))
      (node (ref "X6") (pin "11") (pinfunction "1_11") (pintype "passive"))
    )
    (net (code "6") (name "DEBUG_ACTIVE") (class "Default")
      (node (ref "TP1") (pin "TP") (pinfunction "TP_TP") (pintype "input"))
      (node (ref "U20") (pin "P$64") (pinfunction "PD3_P$64") (pintype "bidirectional"))
    )
    (net (code "7") (name "DEBUG_PC0{slash}TCK{slash}SWCLK") (class "Default")
      (node (ref "R8") (pin "2") (pinfunction "2_2") (pintype "passive"))
      (node (ref "U20") (pin "P$19") (pinfunction "PA2_P$19") (pintype "bidirectional"))
      (node (ref "U20") (pin "P$30") (pinfunction "PF2_P$30") (pintype "bidirectional"))
      (node (ref "U6") (pin "P4") (pinfunction "TCK_P4") (pintype "bidirectional"))
      (node (ref "X1") (pin "9") (pinfunction "1_9") (pintype "passive"))
    )
    (net (code "8") (name "DEBUG_PC1{slash}TMS{slash}SWDIO") (class "Default")
      (node (ref "R10") (pin "2") (pinfunction "2_2") (pintype "passive"))
      (node (ref "U20") (pin "P$20") (pinfunction "PA3_P$20") (pintype "bidirectional"))
      (node (ref "U20") (pin "P$29") (pinfunction "PF1_P$29") (pintype "bidirectional"))
      (node (ref "U6") (pin "P2") (pinfunction "TMS_P2") (pintype "bidirectional"))
      (node (ref "X1") (pin "7") (pinfunction "1_7") (pintype "passive"))
    )
    (net (code "9") (name "DEBUG_PC2{slash}TDI") (class "Default")
      (node (ref "R11") (pin "2") (pinfunction "2_2") (pintype "passive"))
      (node (ref "U20") (pin "P$22") (pinfunction "PA5_P$22") (pintype "bidirectional"))
      (node (ref "U6") (pin "P8") (pinfunction "TDI_P8") (pintype "bidirectional"))
      (node (ref "X1") (pin "5") (pinfunction "1_5") (pintype "passive"))
    )
    (net (code "10") (name "DEBUG_PC3{slash}TDO{slash}SWO") (class "Default")
      (node (ref "R15") (pin "2") (pinfunction "2_2") (pintype "passive"))
      (node (ref "U20") (pin "P$21") (pinfunction "PA4_P$21") (pintype "bidirectional"))
      (node (ref "U20") (pin "P$53") (pinfunction "PD6_P$53") (pintype "bidirectional"))
      (node (ref "U6") (pin "P6") (pinfunction "TDO_P6") (pintype "bidirectional"))
      (node (ref "X1") (pin "3") (pinfunction "1_3") (pintype "passive"))
    )
    (net (code "11") (name "DEBUG_VBUS") (class "Default")
      (node (ref "JP1") (pin "5") (pinfunction "5_5") (pintype "passive"))
      (node (ref "R28") (pin "2") (pinfunction "2_2") (pintype "passive"))
      (node (ref "U22") (pin "P1") (pinfunction "VBUS_P1") (pintype "bidirectional"))
      (node (ref "U3") (pin "6") (pinfunction "VBUS_6") (pintype "passive"))
    )
    (net (code "12") (name "EN0RXI_N") (class "Default")
      (node (ref "R21") (pin "2") (pinfunction "2_2") (pintype "passive"))
      (node (ref "U1") (pin "P$53") (pinfunction "EN0RXIN_P$53") (pintype "bidirectional"))
      (node (ref "U10") (pin "P$8") (pinfunction "P$8_P$8") (pintype "bidirectional"))
    )
    (net (code "13") (name "EN0RXI_P") (class "Default")
      (node (ref "R22") (pin "2") (pinfunction "2_2") (pintype "passive"))
      (node (ref "U1") (pin "P$54") (pinfunction "EN0RXIP_P$54") (pintype "bidirectional"))
      (node (ref "U10") (pin "P$6") (pinfunction "P$6_P$6") (pintype "bidirectional"))
    )
    (net (code "14") (name "EN0TXO_N") (class "Default")
      (node (ref "R23") (pin "2") (pinfunction "2_2") (pintype "passive"))
      (node (ref "U1") (pin "P$56") (pinfunction "EN0TXON_P$56") (pintype "bidirectional"))
      (node (ref "U10") (pin "P$3") (pinfunction "P$3_P$3") (pintype "bidirectional"))
    )
    (net (code "15") (name "EN0TXO_P") (class "Default")
      (node (ref "R24") (pin "2") (pinfunction "2_2") (pintype "passive"))
      (node (ref "U1") (pin "P$57") (pinfunction "EN0TXOP_P$57") (pintype "bidirectional"))
      (node (ref "U10") (pin "P$1") (pinfunction "P$1_P$1") (pintype "bidirectional"))
    )
    (net (code "16") (name "GND") (class "Default")
      (node (ref "C10") (pin "2") (pinfunction "2_2") (pintype "passive"))
      (node (ref "C11") (pin "2") (pinfunction "2_2") (pintype "passive"))
      (node (ref "C12") (pin "2") (pinfunction "2_2") (pintype "passive"))
      (node (ref "C13") (pin "2") (pinfunction "2_2") (pintype "passive"))
      (node (ref "C14") (pin "2") (pinfunction "2_2") (pintype "passive"))
      (node (ref "C15") (pin "2") (pinfunction "2_2") (pintype "passive"))
      (node (ref "C16") (pin "2") (pinfunction "2_2") (pintype "passive"))
      (node (ref "C17") (pin "2") (pinfunction "2_2") (pintype "passive"))
      (node (ref "C18") (pin "2") (pinfunction "2_2") (pintype "passive"))
      (node (ref "C19") (pin "2") (pinfunction "2_2") (pintype "passive"))
      (node (ref "C2") (pin "2") (pinfunction "2_2") (pintype "passive"))
      (node (ref "C20") (pin "2") (pinfunction "2_2") (pintype "passive"))
      (node (ref "C21") (pin "2") (pinfunction "2_2") (pintype "passive"))
      (node (ref "C22") (pin "2") (pinfunction "2_2") (pintype "passive"))
      (node (ref "C23") (pin "2") (pinfunction "2_2") (pintype "passive"))
      (node (ref "C24") (pin "2") (pinfunction "2_2") (pintype "passive"))
      (node (ref "C25") (pin "2") (pinfunction "2_2") (pintype "passive"))
      (node (ref "C26") (pin "2") (pinfunction "2_2") (pintype "passive"))
      (node (ref "C27") (pin "2") (pinfunction "2_2") (pintype "passive"))
      (node (ref "C28") (pin "2") (pinfunction "2_2") (pintype "passive"))
      (node (ref "C29") (pin "2") (pinfunction "2_2") (pintype "passive"))
      (node (ref "C3") (pin "2") (pinfunction "2_2") (pintype "passive"))
      (node (ref "C30") (pin "2") (pinfunction "2_2") (pintype "passive"))
      (node (ref "C31") (pin "2") (pinfunction "2_2") (pintype "passive"))
      (node (ref "C32") (pin "2") (pinfunction "2_2") (pintype "passive"))
      (node (ref "C33") (pin "2") (pinfunction "2_2") (pintype "passive"))
      (node (ref "C4") (pin "2") (pinfunction "2_2") (pintype "passive"))
      (node (ref "C40") (pin "2") (pinfunction "2_2") (pintype "passive"))
      (node (ref "C41") (pin "2") (pinfunction "2_2") (pintype "passive"))
      (node (ref "C42") (pin "2") (pinfunction "2_2") (pintype "passive"))
      (node (ref "C43") (pin "2") (pinfunction "2_2") (pintype "passive"))
      (node (ref "C44") (pin "2") (pinfunction "2_2") (pintype "passive"))
      (node (ref "C45") (pin "2") (pinfunction "2_2") (pintype "passive"))
      (node (ref "C46") (pin "2") (pinfunction "2_2") (pintype "passive"))
      (node (ref "C47") (pin "2") (pinfunction "2_2") (pintype "passive"))
      (node (ref "C48") (pin "2") (pinfunction "2_2") (pintype "passive"))
      (node (ref "C5") (pin "2") (pinfunction "2_2") (pintype "passive"))
      (node (ref "C6") (pin "2") (pinfunction "2_2") (pintype "passive"))
      (node (ref "C7") (pin "2") (pinfunction "2_2") (pintype "passive"))
      (node (ref "C8") (pin "2") (pinfunction "2_2") (pintype "passive"))
      (node (ref "C9") (pin "2") (pinfunction "2_2") (pintype "passive"))
      (node (ref "R12") (pin "2") (pinfunction "2_2") (pintype "passive"))
      (node (ref "R13") (pin "2") (pinfunction "2_2") (pintype "passive"))
      (node (ref "R14") (pin "2") (pinfunction "2_2") (pintype "passive"))
      (node (ref "R25") (pin "2") (pinfunction "2_2") (pintype "passive"))
      (node (ref "R26") (pin "2") (pinfunction "2_2") (pintype "passive"))
      (node (ref "R27") (pin "1") (pinfunction "1_1") (pintype "passive"))
      (node (ref "R29") (pin "1") (pinfunction "1_1") (pintype "passive"))
      (node (ref "R30") (pin "1") (pinfunction "1_1") (pintype "passive"))
      (node (ref "R31") (pin "1") (pinfunction "1_1") (pintype "passive"))
      (node (ref "R33") (pin "1") (pinfunction "1_1") (pintype "passive"))
      (node (ref "R34") (pin "1") (pinfunction "1_1") (pintype "passive"))
      (node (ref "R47") (pin "1") (pinfunction "1_1") (pintype "passive"))
      (node (ref "R52") (pin "1") (pinfunction "1_1") (pintype "passive"))
      (node (ref "R9") (pin "1") (pinfunction "1_1") (pintype "passive"))
      (node (ref "RESET") (pin "P$1") (pinfunction "0_P$1") (pintype "passive"))
      (node (ref "RESET") (pin "P$2") (pinfunction "0_P$2") (pintype "passive"))
      (node (ref "TP14") (pin "TP") (pinfunction "TP_TP") (pintype "input"))
      (node (ref "TP15") (pin "TP") (pinfunction "TP_TP") (pintype "input"))
      (node (ref "TP16") (pin "TP") (pinfunction "TP_TP") (pintype "input"))
      (node (ref "TP17") (pin "TP") (pinfunction "TP_TP") (pintype "input"))
      (node (ref "U1") (pin "P$10") (pinfunction "GNDA_P$10") (pintype "bidirectional"))
      (node (ref "U1") (pin "P$114") (pinfunction "GND_P$114") (pintype "bidirectional"))
      (node (ref "U1") (pin "P$17") (pinfunction "GND_P$17") (pintype "bidirectional"))
      (node (ref "U1") (pin "P$48") (pinfunction "GND_P$48") (pintype "bidirectional"))
      (node (ref "U1") (pin "P$55") (pinfunction "GND_P$55") (pintype "bidirectional"))
      (node (ref "U1") (pin "P$58") (pinfunction "GND_P$58") (pintype "bidirectional"))
      (node (ref "U1") (pin "P$80") (pinfunction "GND_P$80") (pintype "bidirectional"))
      (node (ref "U2") (pin "4") (pinfunction "GND_4") (pintype "power_in"))
      (node (ref "U20") (pin "P$12") (pinfunction "GND0_P$12") (pintype "bidirectional"))
      (node (ref "U20") (pin "P$27") (pinfunction "GND1_P$27") (pintype "bidirectional"))
      (node (ref "U20") (pin "P$3") (pinfunction "GNDA_P$3") (pintype "bidirectional"))
      (node (ref "U20") (pin "P$32") (pinfunction "~{WAKE}_P$32") (pintype "bidirectional"))
      (node (ref "U20") (pin "P$34") (pinfunction "XOSC0_P$34") (pintype "bidirectional"))
      (node (ref "U20") (pin "P$35") (pinfunction "GNDX_P$35") (pintype "bidirectional"))
      (node (ref "U20") (pin "P$39") (pinfunction "GND2_P$39") (pintype "bidirectional"))
      (node (ref "U20") (pin "P$55") (pinfunction "GND3_P$55") (pintype "bidirectional"))
      (node (ref "U21") (pin "3") (pinfunction "GND_3") (pintype "bidirectional"))
      (node (ref "U21") (pin "5") (pinfunction "NC_5") (pintype "bidirectional"))
      (node (ref "U21") (pin "9") (pinfunction "~{TRST}_9") (pintype "bidirectional"))
      (node (ref "U22") (pin "P5") (pinfunction "GND_P5") (pintype "bidirectional"))
      (node (ref "U3") (pin "4") (pinfunction "GND_4") (pintype "power_in"))
      (node (ref "U4") (pin "1") (pinfunction "GND_1") (pintype "power_in"))
      (node (ref "U4") (pin "9") (pinfunction "EPAD_9") (pintype "passive"))
      (node (ref "U4") (pin "V") (pinfunction "VIA_V") (pintype "bidirectional"))
      (node (ref "U4") (pin "V_2") (pinfunction "VIA_V_2") (pintype "bidirectional"))
      (node (ref "U4") (pin "V_3") (pinfunction "VIA_V_3") (pintype "bidirectional"))
      (node (ref "U4") (pin "V_4") (pinfunction "VIA_V_4") (pintype "bidirectional"))
      (node (ref "U4") (pin "V_5") (pinfunction "VIA_V_5") (pintype "bidirectional"))
      (node (ref "U4") (pin "V_6") (pinfunction "VIA_V_6") (pintype "bidirectional"))
      (node (ref "U5") (pin "3") (pinfunction "GND_3") (pintype "power_in"))
      (node (ref "U5") (pin "7") (pinfunction "EPAD_7") (pintype "passive"))
      (node (ref "U5") (pin "V") (pinfunction "VIA_V") (pintype "bidirectional"))
      (node (ref "U5") (pin "V_2") (pinfunction "VIA_V_2") (pintype "bidirectional"))
      (node (ref "U6") (pin "P5") (pinfunction "GND_P5") (pintype "bidirectional"))
      (node (ref "U6") (pin "P9") (pinfunction "GND1_P9") (pintype "bidirectional"))
      (node (ref "U7") (pin "P5") (pinfunction "GND_P5") (pintype "bidirectional"))
      (node (ref "USR_SW1") (pin "P$3") (pinfunction "1_P$3") (pintype "passive"))
      (node (ref "USR_SW1") (pin "P$4") (pinfunction "1_P$4") (pintype "passive"))
      (node (ref "USR_SW2") (pin "P$3") (pinfunction "1_P$3") (pintype "passive"))
      (node (ref "USR_SW2") (pin "P$4") (pinfunction "1_P$4") (pintype "passive"))
      (node (ref "WAKE") (pin "P$3") (pinfunction "1_P$3") (pintype "passive"))
      (node (ref "WAKE") (pin "P$4") (pinfunction "1_P$4") (pintype "passive"))
      (node (ref "X11") (pin "3") (pinfunction "1_3") (pintype "passive"))
      (node (ref "X11") (pin "35") (pinfunction "1_35") (pintype "passive"))
      (node (ref "X11") (pin "36") (pinfunction "1_36") (pintype "passive"))
      (node (ref "X11") (pin "4") (pinfunction "1_4") (pintype "passive"))
      (node (ref "X11") (pin "61") (pinfunction "1_61") (pintype "passive"))
      (node (ref "X11") (pin "62") (pinfunction "1_62") (pintype "passive"))
      (node (ref "X11") (pin "96") (pinfunction "1_96") (pintype "passive"))
      (node (ref "X6") (pin "4") (pinfunction "1_4") (pintype "passive"))
      (node (ref "X7") (pin "2") (pinfunction "1_2") (pintype "passive"))
      (node (ref "X8") (pin "4") (pinfunction "1_4") (pintype "passive"))
      (node (ref "X9") (pin "2") (pinfunction "1_2") (pintype "passive"))
    )
    (net (code "17") (name "ICDI_RESET") (class "Default")
      (node (ref "C2") (pin "1") (pinfunction "1_1") (pintype "passive"))
      (node (ref "R3") (pin "1") (pinfunction "1_1") (pintype "passive"))
      (node (ref "U20") (pin "P$38") (pinfunction "~{RESET}_P$38") (pintype "bidirectional"))
      (node (ref "U21") (pin "10") (pinfunction "RESET_10") (pintype "bidirectional"))
    )
    (net (code "18") (name "ICDI_TCK") (class "Default")
      (node (ref "R4") (pin "2") (pinfunction "2_2") (pintype "passive"))
      (node (ref "U20") (pin "P$52") (pinfunction "PC0/TCK_P$52") (pintype "bidirectional"))
      (node (ref "U21") (pin "4") (pinfunction "TCK_4") (pintype "bidirectional"))
    )
    (net (code "19") (name "ICDI_TDI") (class "Default")
      (node (ref "U20") (pin "P$50") (pinfunction "PC2/TDI_P$50") (pintype "bidirectional"))
      (node (ref "U21") (pin "8") (pinfunction "TDI_8") (pintype "bidirectional"))
    )
    (net (code "20") (name "ICDI_TDO") (class "Default")
      (node (ref "U20") (pin "P$49") (pinfunction "PC3/TDO_P$49") (pintype "bidirectional"))
      (node (ref "U21") (pin "6") (pinfunction "TDO_6") (pintype "bidirectional"))
    )
    (net (code "21") (name "ICDI_TMS") (class "Default")
      (node (ref "R5") (pin "2") (pinfunction "2_2") (pintype "passive"))
      (node (ref "U20") (pin "P$51") (pinfunction "PC1/TMS_P$51") (pintype "bidirectional"))
      (node (ref "U21") (pin "2") (pinfunction "TMS_2") (pintype "bidirectional"))
    )
    (net (code "22") (name "ICDI_USBD_N") (class "Default")
      (node (ref "U20") (pin "P$43") (pinfunction "PD4_P$43") (pintype "bidirectional"))
      (node (ref "U22") (pin "P2") (pinfunction "DM_P2") (pintype "bidirectional"))
      (node (ref "U3") (pin "2") (pinfunction "D-_2") (pintype "passive"))
    )
    (net (code "23") (name "ICDI_USBD_P") (class "Default")
      (node (ref "U20") (pin "P$44") (pinfunction "PD5_P$44") (pintype "bidirectional"))
      (node (ref "U22") (pin "P3") (pinfunction "DP_P3") (pintype "bidirectional"))
      (node (ref "U3") (pin "1") (pinfunction "D+_1") (pintype "passive"))
    )
    (net (code "24") (name "ICDI_VDDC") (class "Default")
      (node (ref "C5") (pin "1") (pinfunction "1_1") (pintype "passive"))
      (node (ref "C6") (pin "1") (pinfunction "1_1") (pintype "passive"))
      (node (ref "C7") (pin "1") (pinfunction "1_1") (pintype "passive"))
      (node (ref "U20") (pin "P$25") (pinfunction "VDDC0_P$25") (pintype "bidirectional"))
      (node (ref "U20") (pin "P$56") (pinfunction "VDDC1_P$56") (pintype "bidirectional"))
    )
    (net (code "25") (name "MCU_3V3") (class "Default")
      (node (ref "C16") (pin "1") (pinfunction "1_1") (pintype "passive"))
      (node (ref "C17") (pin "1") (pinfunction "1_1") (pintype "passive"))
      (node (ref "C18") (pin "1") (pinfunction "1_1") (pintype "passive"))
      (node (ref "C22") (pin "1") (pinfunction "1_1") (pintype "passive"))
      (node (ref "C40") (pin "1") (pinfunction "1_1") (pintype "passive"))
      (node (ref "C41") (pin "1") (pinfunction "1_1") (pintype "passive"))
      (node (ref "C42") (pin "1") (pinfunction "1_1") (pintype "passive"))
      (node (ref "C43") (pin "1") (pinfunction "1_1") (pintype "passive"))
      (node (ref "JP2") (pin "2") (pinfunction "2_2") (pintype "passive"))
      (node (ref "R1") (pin "1") (pinfunction "1_1") (pintype "passive"))
      (node (ref "R2") (pin "1") (pinfunction "1_1") (pintype "passive"))
      (node (ref "R21") (pin "1") (pinfunction "1_1") (pintype "passive"))
      (node (ref "R22") (pin "1") (pinfunction "1_1") (pintype "passive"))
      (node (ref "R23") (pin "1") (pinfunction "1_1") (pintype "passive"))
      (node (ref "R24") (pin "1") (pinfunction "1_1") (pintype "passive"))
      (node (ref "R39") (pin "2") (pinfunction "2_2") (pintype "passive"))
      (node (ref "R41") (pin "2") (pinfunction "2_2") (pintype "passive"))
      (node (ref "R44") (pin "1") (pinfunction "1_1") (pintype "passive"))
      (node (ref "U1") (pin "P$101") (pinfunction "VDD_P$101") (pintype "bidirectional"))
      (node (ref "U1") (pin "P$113") (pinfunction "VDD_P$113") (pintype "bidirectional"))
      (node (ref "U1") (pin "P$122") (pinfunction "VDD_P$122") (pintype "bidirectional"))
      (node (ref "U1") (pin "P$16") (pinfunction "VDD_P$16") (pintype "bidirectional"))
      (node (ref "U1") (pin "P$26") (pinfunction "VDD_P$26") (pintype "bidirectional"))
      (node (ref "U1") (pin "P$28") (pinfunction "VDD_P$28") (pintype "bidirectional"))
      (node (ref "U1") (pin "P$39") (pinfunction "VDD_P$39") (pintype "bidirectional"))
      (node (ref "U1") (pin "P$47") (pinfunction "VDD_P$47") (pintype "bidirectional"))
      (node (ref "U1") (pin "P$51") (pinfunction "VDD_P$51") (pintype "bidirectional"))
      (node (ref "U1") (pin "P$52") (pinfunction "VDD_P$52") (pintype "bidirectional"))
      (node (ref "U1") (pin "P$69") (pinfunction "VDD_P$69") (pintype "bidirectional"))
      (node (ref "U1") (pin "P$7") (pinfunction "VDD_P$7") (pintype "bidirectional"))
      (node (ref "U1") (pin "P$79") (pinfunction "VDD_P$79") (pintype "bidirectional"))
      (node (ref "U1") (pin "P$8") (pinfunction "VDDA_P$8") (pintype "bidirectional"))
      (node (ref "U1") (pin "P$90") (pinfunction "VDD_P$90") (pintype "bidirectional"))
      (node (ref "U10") (pin "P$2") (pinfunction "P$2_P$2") (pintype "bidirectional"))
      (node (ref "U10") (pin "P$7") (pinfunction "P$7_P$7") (pintype "bidirectional"))
    )
    (net (code "26") (name "Net-(C1-Pad1)") (class "Default")
      (node (ref "C1") (pin "1") (pinfunction "1_1") (pintype "passive"))
      (node (ref "R32") (pin "1") (pinfunction "1_1") (pintype "passive"))
      (node (ref "R43") (pin "1") (pinfunction "1_1") (pintype "passive"))
      (node (ref "R45") (pin "1") (pinfunction "1_1") (pintype "passive"))
      (node (ref "R46") (pin "1") (pinfunction "1_1") (pintype "passive"))
    )
    (net (code "27") (name "Net-(C1-Pad2)") (class "Default")
      (node (ref "C1") (pin "2") (pinfunction "2_2") (pintype "passive"))
      (node (ref "C31") (pin "1") (pinfunction "1_1") (pintype "passive"))
      (node (ref "R47") (pin "2") (pinfunction "2_2") (pintype "passive"))
      (node (ref "U14") (pin "10") (pinfunction "CHASSIS_10") (pintype "bidirectional"))
      (node (ref "U14") (pin "9") (pinfunction "CHASSIS_9") (pintype "bidirectional"))
    )
    (net (code "28") (name "Net-(C14-Pad1)") (class "Default")
      (node (ref "C14") (pin "1") (pinfunction "1_1") (pintype "passive"))
      (node (ref "C15") (pin "1") (pinfunction "1_1") (pintype "passive"))
      (node (ref "C4") (pin "1") (pinfunction "1_1") (pintype "passive"))
      (node (ref "TP12") (pin "TP") (pinfunction "TP_TP") (pintype "input"))
      (node (ref "U1") (pin "P$115") (pinfunction "VDDC_P$115") (pintype "bidirectional"))
      (node (ref "U1") (pin "P$87") (pinfunction "VDDC_P$87") (pintype "bidirectional"))
    )
    (net (code "29") (name "Net-(D0-PadC)") (class "Default")
      (node (ref "D0") (pin "C") (pinfunction "C_C") (pintype "passive"))
      (node (ref "R9") (pin "2") (pinfunction "2_2") (pintype "passive"))
    )
    (net (code "30") (name "Net-(D1-PadC)") (class "Default")
      (node (ref "D1") (pin "C") (pinfunction "C_C") (pintype "passive"))
      (node (ref "R33") (pin "2") (pinfunction "2_2") (pintype "passive"))
    )
    (net (code "31") (name "Net-(D2-PadC)") (class "Default")
      (node (ref "D2") (pin "C") (pinfunction "C_C") (pintype "passive"))
      (node (ref "R27") (pin "2") (pinfunction "2_2") (pintype "passive"))
    )
    (net (code "32") (name "Net-(D3-PadC)") (class "Default")
      (node (ref "D3") (pin "C") (pinfunction "C_C") (pintype "passive"))
      (node (ref "R31") (pin "2") (pinfunction "2_2") (pintype "passive"))
    )
    (net (code "33") (name "Net-(D4-PadC)") (class "Default")
      (node (ref "D4") (pin "C") (pinfunction "C_C") (pintype "passive"))
      (node (ref "R30") (pin "2") (pinfunction "2_2") (pintype "passive"))
    )
    (net (code "34") (name "Net-(R32-Pad2)") (class "Default")
      (node (ref "R32") (pin "2") (pinfunction "2_2") (pintype "passive"))
      (node (ref "U10") (pin "P$15") (pinfunction "P$15_P$15") (pintype "bidirectional"))
    )
    (net (code "35") (name "Net-(R38-Pad1)") (class "Default")
      (node (ref "R38") (pin "1") (pinfunction "1_1") (pintype "passive"))
      (node (ref "R39") (pin "1") (pinfunction "1_1") (pintype "passive"))
      (node (ref "R42") (pin "1") (pinfunction "1_1") (pintype "passive"))
      (node (ref "TP11") (pin "TP") (pinfunction "TP_TP") (pintype "input"))
    )
    (net (code "36") (name "Net-(R43-Pad2)") (class "Default")
      (node (ref "R43") (pin "2") (pinfunction "2_2") (pintype "passive"))
      (node (ref "U10") (pin "P$10") (pinfunction "P$10_P$10") (pintype "bidirectional"))
    )
    (net (code "37") (name "Net-(U1B-OSC0)") (class "Default")
      (node (ref "C44") (pin "1") (pinfunction "1_1") (pintype "passive"))
      (node (ref "U1") (pin "P$88") (pinfunction "OSC0_P$88") (pintype "bidirectional"))
      (node (ref "Y1") (pin "P$3") (pinfunction "OSC1_P$3") (pintype "bidirectional"))
    )
    (net (code "38") (name "Net-(U1B-OSC1)") (class "Default")
      (node (ref "R49") (pin "2") (pinfunction "2_2") (pintype "passive"))
      (node (ref "U1") (pin "P$89") (pinfunction "OSC1_P$89") (pintype "bidirectional"))
    )
    (net (code "39") (name "Net-(U1B-VBAT)") (class "Default")
      (node (ref "C3") (pin "1") (pinfunction "1_1") (pintype "passive"))
      (node (ref "R38") (pin "2") (pinfunction "2_2") (pintype "passive"))
      (node (ref "U1") (pin "P$68") (pinfunction "VBAT_P$68") (pintype "bidirectional"))
    )
    (net (code "40") (name "Net-(U1B-XOSC0)") (class "Default")
      (node (ref "C48") (pin "1") (pinfunction "1_1") (pintype "passive"))
      (node (ref "U1") (pin "P$66") (pinfunction "XOSC0_P$66") (pintype "bidirectional"))
      (node (ref "Y3") (pin "P$1") (pinfunction "P$1_P$1") (pintype "bidirectional"))
    )
    (net (code "41") (name "Net-(U1B-XOSC1)") (class "Default")
      (node (ref "C47") (pin "1") (pinfunction "1_1") (pintype "passive"))
      (node (ref "U1") (pin "P$67") (pinfunction "XOSC1_P$67") (pintype "bidirectional"))
      (node (ref "Y3") (pin "P$2") (pinfunction "P$2_P$2") (pintype "bidirectional"))
    )
    (net (code "42") (name "Net-(U1B-~{HIB})") (class "Default")
      (node (ref "TP9") (pin "TP") (pinfunction "TP_TP") (pintype "input"))
      (node (ref "U1") (pin "P$65") (pinfunction "~{HIB}_P$65") (pintype "bidirectional"))
    )
    (net (code "43") (name "Net-(U1B-~{RESET})") (class "Default")
      (node (ref "C46") (pin "1") (pinfunction "1_1") (pintype "passive"))
      (node (ref "R44") (pin "2") (pinfunction "2_2") (pintype "passive"))
      (node (ref "R51") (pin "2") (pinfunction "2_2") (pintype "passive"))
      (node (ref "U1") (pin "P$70") (pinfunction "~{RESET}_P$70") (pintype "bidirectional"))
    )
    (net (code "44") (name "Net-(U4-*EN1)") (class "Default")
      (node (ref "R26") (pin "1") (pinfunction "1_1") (pintype "passive"))
      (node (ref "R35") (pin "2") (pinfunction "2_2") (pintype "passive"))
      (node (ref "U4") (pin "3") (pinfunction "*EN1_3") (pintype "input"))
    )
    (net (code "45") (name "Net-(U4-*OC1)") (class "Default")
      (node (ref "R36") (pin "1") (pinfunction "1_1") (pintype "passive"))
      (node (ref "TP8") (pin "TP") (pinfunction "TP_TP") (pintype "input"))
      (node (ref "U4") (pin "8") (pinfunction "*OC1_8") (pintype "output"))
    )
    (net (code "46") (name "Net-(U5-EN)") (class "Default")
      (node (ref "R17") (pin "2") (pinfunction "2_2") (pintype "passive"))
      (node (ref "TP3") (pin "TP") (pinfunction "TP_TP") (pintype "input"))
      (node (ref "U5") (pin "4") (pinfunction "EN_4") (pintype "passive"))
    )
    (net (code "47") (name "Net-(U5-NR{slash}FB)") (class "Default")
      (node (ref "C19") (pin "1") (pinfunction "1_1") (pintype "passive"))
      (node (ref "R48") (pin "1") (pinfunction "1_1") (pintype "passive"))
      (node (ref "U5") (pin "2") (pinfunction "NR/FB_2") (pintype "bidirectional"))
    )
    (net (code "48") (name "Net-(U5-OUT)") (class "Default")
      (node (ref "C20") (pin "1") (pinfunction "1_1") (pintype "passive"))
      (node (ref "JP3") (pin "2") (pinfunction "2_2") (pintype "passive"))
      (node (ref "R48") (pin "2") (pinfunction "2_2") (pintype "passive"))
      (node (ref "U5") (pin "1") (pinfunction "OUT_1") (pintype "output"))
    )
    (net (code "49") (name "Net-(U6-~{EXTDBG})") (class "Default")
      (node (ref "R40") (pin "2") (pinfunction "2_2") (pintype "passive"))
      (node (ref "U6") (pin "P3") (pinfunction "~{EXTDBG}_P3") (pintype "bidirectional"))
    )
    (net (code "50") (name "Net-(U7B-S1)") (class "Default")
      (node (ref "C32") (pin "1") (pinfunction "1_1") (pintype "passive"))
      (node (ref "R52") (pin "2") (pinfunction "2_2") (pintype "passive"))
      (node (ref "U7") (pin "P$1") (pinfunction "S1_P$1") (pintype "passive"))
      (node (ref "U7") (pin "P$2") (pinfunction "S2_P$2") (pintype "passive"))
      (node (ref "U7") (pin "P$3") (pinfunction "S3_P$3") (pintype "passive"))
      (node (ref "U7") (pin "P$4") (pinfunction "S4_P$4") (pintype "passive"))
      (node (ref "U7") (pin "P$5") (pinfunction "S5_P$5") (pintype "passive"))
      (node (ref "U7") (pin "P$6") (pinfunction "S6_P$6") (pintype "passive"))
    )
    (net (code "51") (name "Net-(U13-P$1)") (class "Default")
      (node (ref "U10") (pin "P$16") (pinfunction "P$16_P$16") (pintype "bidirectional"))
      (node (ref "U13") (pin "1") (pinfunction "P$1_1") (pintype "bidirectional"))
      (node (ref "U13") (pin "8") (pinfunction "P$8_8") (pintype "bidirectional"))
      (node (ref "U14") (pin "1") (pinfunction "TX+_1") (pintype "bidirectional"))
    )
    (net (code "52") (name "Net-(U13-P$2)") (class "Default")
      (node (ref "U10") (pin "P$14") (pinfunction "P$14_P$14") (pintype "bidirectional"))
      (node (ref "U13") (pin "2") (pinfunction "P$2_2") (pintype "bidirectional"))
      (node (ref "U13") (pin "7") (pinfunction "P$7_7") (pintype "bidirectional"))
      (node (ref "U14") (pin "2") (pinfunction "TX-_2") (pintype "bidirectional"))
    )
    (net (code "53") (name "Net-(U13-P$3)") (class "Default")
      (node (ref "U10") (pin "P$11") (pinfunction "P$11_P$11") (pintype "bidirectional"))
      (node (ref "U13") (pin "3") (pinfunction "P$3_3") (pintype "bidirectional"))
      (node (ref "U13") (pin "6") (pinfunction "P$6_6") (pintype "bidirectional"))
      (node (ref "U14") (pin "3") (pinfunction "RX+_3") (pintype "bidirectional"))
    )
    (net (code "54") (name "Net-(U13-P$4)") (class "Default")
      (node (ref "U10") (pin "P$9") (pinfunction "P$9_P$9") (pintype "bidirectional"))
      (node (ref "U13") (pin "4") (pinfunction "P$4_4") (pintype "bidirectional"))
      (node (ref "U13") (pin "5") (pinfunction "P$5_5") (pintype "bidirectional"))
      (node (ref "U14") (pin "6") (pinfunction "RX-_6") (pintype "bidirectional"))
    )
    (net (code "55") (name "Net-(U14-TERM1A)") (class "Default")
      (node (ref "R45") (pin "2") (pinfunction "2_2") (pintype "passive"))
      (node (ref "U14") (pin "4") (pinfunction "TERM1A_4") (pintype "bidirectional"))
      (node (ref "U14") (pin "5") (pinfunction "TERM1B_5") (pintype "bidirectional"))
    )
    (net (code "56") (name "Net-(U14-TERM2A)") (class "Default")
      (node (ref "R46") (pin "2") (pinfunction "2_2") (pintype "passive"))
      (node (ref "U14") (pin "7") (pinfunction "TERM2A_7") (pintype "bidirectional"))
      (node (ref "U14") (pin "8") (pinfunction "TERM2B_8") (pintype "bidirectional"))
    )
    (net (code "57") (name "Net-(U20-OSC0)") (class "Default")
      (node (ref "C9") (pin "1") (pinfunction "1_1") (pintype "passive"))
      (node (ref "U20") (pin "P$40") (pinfunction "OSC0_P$40") (pintype "bidirectional"))
      (node (ref "Y2") (pin "P$1") (pinfunction "OSC0_P$1") (pintype "bidirectional"))
    )
    (net (code "58") (name "Net-(U20-OSC1)") (class "Default")
      (node (ref "R50") (pin "1") (pinfunction "1_1") (pintype "passive"))
      (node (ref "U20") (pin "P$41") (pinfunction "OSC1_P$41") (pintype "bidirectional"))
    )
    (net (code "59") (name "Net-(U20-PB1)") (class "Default")
      (node (ref "R28") (pin "1") (pinfunction "1_1") (pintype "passive"))
      (node (ref "R29") (pin "2") (pinfunction "2_2") (pintype "passive"))
      (node (ref "U20") (pin "P$46") (pinfunction "PB1_P$46") (pintype "bidirectional"))
    )
    (net (code "60") (name "Net-(U22B-S1)") (class "Default")
      (node (ref "C33") (pin "1") (pinfunction "1_1") (pintype "passive"))
      (node (ref "R34") (pin "2") (pinfunction "2_2") (pintype "passive"))
      (node (ref "U22") (pin "P10") (pinfunction "S5_P10") (pintype "passive"))
      (node (ref "U22") (pin "P11") (pinfunction "S6_P11") (pintype "passive"))
      (node (ref "U22") (pin "P6") (pinfunction "S1_P6") (pintype "passive"))
      (node (ref "U22") (pin "P7") (pinfunction "S2_P7") (pintype "passive"))
      (node (ref "U22") (pin "P8") (pinfunction "S3_P8") (pintype "passive"))
      (node (ref "U22") (pin "P9") (pinfunction "S4_P9") (pintype "passive"))
    )
    (net (code "61") (name "Net-(Y1-OSC0)") (class "Default")
      (node (ref "C45") (pin "1") (pinfunction "1_1") (pintype "passive"))
      (node (ref "R49") (pin "1") (pinfunction "1_1") (pintype "passive"))
      (node (ref "Y1") (pin "P$1") (pinfunction "OSC0_P$1") (pintype "bidirectional"))
    )
    (net (code "62") (name "Net-(Y2-OSC1)") (class "Default")
      (node (ref "C8") (pin "1") (pinfunction "1_1") (pintype "passive"))
      (node (ref "R50") (pin "2") (pinfunction "2_2") (pintype "passive"))
      (node (ref "Y2") (pin "P$3") (pinfunction "OSC1_P$3") (pintype "bidirectional"))
    )
    (net (code "63") (name "PA0") (class "Default")
      (node (ref "JP4") (pin "2") (pinfunction "2_2") (pintype "passive"))
      (node (ref "U1") (pin "P$33") (pinfunction "PA0_P$33") (pintype "bidirectional"))
      (node (ref "X11") (pin "74") (pinfunction "1_74") (pintype "passive"))
    )
    (net (code "64") (name "PA1") (class "Default")
      (node (ref "JP5") (pin "2") (pinfunction "2_2") (pintype "passive"))
      (node (ref "U1") (pin "P$34") (pinfunction "PA1_P$34") (pintype "bidirectional"))
      (node (ref "X11") (pin "76") (pinfunction "1_76") (pintype "passive"))
    )
    (net (code "65") (name "PA2") (class "Default")
      (node (ref "R20") (pin "2") (pinfunction "2_2") (pintype "passive"))
      (node (ref "U1") (pin "P$35") (pinfunction "PA2_P$35") (pintype "bidirectional"))
      (node (ref "X11") (pin "6") (pinfunction "1_6") (pintype "passive"))
    )
    (net (code "66") (name "PA3") (class "Default")
      (node (ref "R19") (pin "2") (pinfunction "2_2") (pintype "passive"))
      (node (ref "U1") (pin "P$36") (pinfunction "PA3_P$36") (pintype "bidirectional"))
      (node (ref "X11") (pin "8") (pinfunction "1_8") (pintype "passive"))
    )
    (net (code "67") (name "PA4") (class "Default")
      (node (ref "U1") (pin "P$37") (pinfunction "PA4_P$37") (pintype "bidirectional"))
      (node (ref "X11") (pin "10") (pinfunction "1_10") (pintype "passive"))
      (node (ref "X6") (pin "18") (pinfunction "1_18") (pintype "passive"))
    )
    (net (code "68") (name "PA5") (class "Default")
      (node (ref "U1") (pin "P$38") (pinfunction "PA5_P$38") (pintype "bidirectional"))
      (node (ref "X11") (pin "12") (pinfunction "1_12") (pintype "passive"))
      (node (ref "X6") (pin "20") (pinfunction "1_20") (pintype "passive"))
    )
    (net (code "69") (name "PA6") (class "Default")
      (node (ref "U1") (pin "P$40") (pinfunction "PA6_P$40") (pintype "bidirectional"))
      (node (ref "X11") (pin "25") (pinfunction "1_25") (pintype "passive"))
      (node (ref "X8") (pin "16") (pinfunction "1_16") (pintype "passive"))
    )
    (net (code "70") (name "PA7") (class "Default")
      (node (ref "U1") (pin "P$41") (pinfunction "PA7_P$41") (pintype "bidirectional"))
      (node (ref "X11") (pin "27") (pinfunction "1_27") (pintype "passive"))
      (node (ref "X7") (pin "8") (pinfunction "1_8") (pintype "passive"))
    )
    (net (code "71") (name "PB0") (class "Default")
      (node (ref "R18") (pin "1") (pinfunction "1_1") (pintype "passive"))
      (node (ref "U1") (pin "P$95") (pinfunction "PB0_P$95") (pintype "bidirectional"))
      (node (ref "X11") (pin "58") (pinfunction "1_58") (pintype "passive"))
    )
    (net (code "72") (name "PB2") (class "Default")
      (node (ref "U1") (pin "P$91") (pinfunction "PB2_P$91") (pintype "bidirectional"))
      (node (ref "X11") (pin "67") (pinfunction "1_67") (pintype "passive"))
      (node (ref "X8") (pin "17") (pinfunction "1_17") (pintype "passive"))
    )
    (net (code "73") (name "PB3") (class "Default")
      (node (ref "U1") (pin "P$92") (pinfunction "PB3_P$92") (pintype "bidirectional"))
      (node (ref "X11") (pin "69") (pinfunction "1_69") (pintype "passive"))
      (node (ref "X8") (pin "19") (pinfunction "1_19") (pintype "passive"))
    )
    (net (code "74") (name "PB4") (class "Default")
      (node (ref "U1") (pin "P$121") (pinfunction "PB4_P$121") (pintype "bidirectional"))
      (node (ref "X11") (pin "5") (pinfunction "1_5") (pintype "passive"))
      (node (ref "X6") (pin "6") (pinfunction "1_6") (pintype "passive"))
    )
    (net (code "75") (name "PB5") (class "Default")
      (node (ref "U1") (pin "P$120") (pinfunction "PB5_P$120") (pintype "bidirectional"))
      (node (ref "X11") (pin "7") (pinfunction "1_7") (pintype "passive"))
      (node (ref "X6") (pin "8") (pinfunction "1_8") (pintype "passive"))
    )
    (net (code "76") (name "PC4") (class "Default")
      (node (ref "U1") (pin "P$25") (pinfunction "PC4_P$25") (pintype "bidirectional"))
      (node (ref "X11") (pin "23") (pinfunction "1_23") (pintype "passive"))
      (node (ref "X8") (pin "5") (pinfunction "1_5") (pintype "passive"))
    )
    (net (code "77") (name "PC5") (class "Default")
      (node (ref "U1") (pin "P$24") (pinfunction "PC5_P$24") (pintype "bidirectional"))
      (node (ref "X11") (pin "21") (pinfunction "1_21") (pintype "passive"))
      (node (ref "X8") (pin "7") (pinfunction "1_7") (pintype "passive"))
    )
    (net (code "78") (name "PC6") (class "Default")
      (node (ref "U1") (pin "P$23") (pinfunction "PC6_P$23") (pintype "bidirectional"))
      (node (ref "X11") (pin "19") (pinfunction "1_19") (pintype "passive"))
      (node (ref "X8") (pin "9") (pinfunction "1_9") (pintype "passive"))
    )
    (net (code "79") (name "PC7") (class "Default")
      (node (ref "U1") (pin "P$22") (pinfunction "PC7_P$22") (pintype "bidirectional"))
      (node (ref "X11") (pin "17") (pinfunction "1_17") (pintype "passive"))
      (node (ref "X8") (pin "15") (pinfunction "1_15") (pintype "passive"))
    )
    (net (code "80") (name "PD0") (class "Default")
      (node (ref "U1") (pin "P$1") (pinfunction "PD0_P$1") (pintype "bidirectional"))
      (node (ref "X11") (pin "50") (pinfunction "1_50") (pintype "passive"))
      (node (ref "X9") (pin "14") (pinfunction "1_14") (pintype "passive"))
    )
    (net (code "81") (name "PD1") (class "Default")
      (node (ref "U1") (pin "P$2") (pinfunction "PD1_P$2") (pintype "bidirectional"))
      (node (ref "X11") (pin "48") (pinfunction "1_48") (pintype "passive"))
      (node (ref "X9") (pin "12") (pinfunction "1_12") (pintype "passive"))
    )
    (net (code "82") (name "PD2") (class "Default")
      (node (ref "U1") (pin "P$3") (pinfunction "PD2_P$3") (pintype "bidirectional"))
      (node (ref "X11") (pin "52") (pinfunction "1_52") (pintype "passive"))
      (node (ref "X6") (pin "3") (pinfunction "1_3") (pintype "passive"))
    )
    (net (code "83") (name "PD3") (class "Default")
      (node (ref "U1") (pin "P$4") (pinfunction "PD3_P$4") (pintype "bidirectional"))
      (node (ref "X11") (pin "46") (pinfunction "1_46") (pintype "passive"))
      (node (ref "X8") (pin "13") (pinfunction "1_13") (pintype "passive"))
    )
    (net (code "84") (name "PD4") (class "Default")
      (node (ref "JP4") (pin "3") (pinfunction "3_3") (pintype "passive"))
      (node (ref "U1") (pin "P$125") (pinfunction "PD4_P$125") (pintype "bidirectional"))
      (node (ref "X11") (pin "40") (pinfunction "1_40") (pintype "passive"))
    )
    (net (code "85") (name "PD5") (class "Default")
      (node (ref "JP5") (pin "3") (pinfunction "3_3") (pintype "passive"))
      (node (ref "U1") (pin "P$126") (pinfunction "PD5_P$126") (pintype "bidirectional"))
      (node (ref "X11") (pin "38") (pinfunction "1_38") (pintype "passive"))
    )
    (net (code "86") (name "PD6") (class "Default")
      (node (ref "U1") (pin "P$127") (pinfunction "PD6_P$127") (pintype "bidirectional"))
      (node (ref "U4") (pin "4") (pinfunction "*EN2_4") (pintype "input"))
      (node (ref "X11") (pin "44") (pinfunction "1_44") (pintype "passive"))
    )
    (net (code "87") (name "PD7") (class "Default")
      (node (ref "U1") (pin "P$128") (pinfunction "PD7_P$128") (pintype "bidirectional"))
      (node (ref "X11") (pin "42") (pinfunction "1_42") (pintype "passive"))
      (node (ref "X8") (pin "14") (pinfunction "1_14") (pintype "passive"))
    )
    (net (code "88") (name "PE0") (class "Default")
      (node (ref "U1") (pin "P$15") (pinfunction "PE0_P$15") (pintype "bidirectional"))
      (node (ref "X11") (pin "14") (pinfunction "1_14") (pintype "passive"))
      (node (ref "X8") (pin "6") (pinfunction "1_6") (pintype "passive"))
    )
    (net (code "89") (name "PE1") (class "Default")
      (node (ref "U1") (pin "P$14") (pinfunction "PE1_P$14") (pintype "bidirectional"))
      (node (ref "X11") (pin "16") (pinfunction "1_16") (pintype "passive"))
      (node (ref "X8") (pin "8") (pinfunction "1_8") (pintype "passive"))
    )
    (net (code "90") (name "PE2") (class "Default")
      (node (ref "U1") (pin "P$13") (pinfunction "PE2_P$13") (pintype "bidirectional"))
      (node (ref "X11") (pin "18") (pinfunction "1_18") (pintype "passive"))
      (node (ref "X8") (pin "10") (pinfunction "1_10") (pintype "passive"))
    )
    (net (code "91") (name "PE3") (class "Default")
      (node (ref "U1") (pin "P$12") (pinfunction "PE3_P$12") (pintype "bidirectional"))
      (node (ref "X11") (pin "20") (pinfunction "1_20") (pintype "passive"))
      (node (ref "X8") (pin "12") (pinfunction "1_12") (pintype "passive"))
    )
    (net (code "92") (name "PE4") (class "Default")
      (node (ref "U1") (pin "P$123") (pinfunction "PE4_P$123") (pintype "bidirectional"))
      (node (ref "X11") (pin "22") (pinfunction "1_22") (pintype "passive"))
      (node (ref "X8") (pin "3") (pinfunction "1_3") (pintype "passive"))
    )
    (net (code "93") (name "PE5") (class "Default")
      (node (ref "U1") (pin "P$124") (pinfunction "PE5_P$124") (pintype "bidirectional"))
      (node (ref "X11") (pin "24") (pinfunction "1_24") (pintype "passive"))
      (node (ref "X8") (pin "11") (pinfunction "1_11") (pintype "passive"))
    )
    (net (code "94") (name "PF0") (class "Default")
      (node (ref "D4") (pin "A") (pinfunction "A_A") (pintype "passive"))
      (node (ref "U1") (pin "P$42") (pinfunction "PF0_P$42") (pintype "bidirectional"))
      (node (ref "X11") (pin "66") (pinfunction "1_66") (pintype "passive"))
    )
    (net (code "95") (name "PF1") (class "Default")
      (node (ref "U1") (pin "P$43") (pinfunction "PF1_P$43") (pintype "bidirectional"))
      (node (ref "X11") (pin "68") (pinfunction "1_68") (pintype "passive"))
      (node (ref "X9") (pin "1") (pinfunction "1_1") (pintype "passive"))
    )
    (net (code "96") (name "PF2") (class "Default")
      (node (ref "U1") (pin "P$44") (pinfunction "PF2_P$44") (pintype "bidirectional"))
      (node (ref "X11") (pin "70") (pinfunction "1_70") (pintype "passive"))
      (node (ref "X9") (pin "3") (pinfunction "1_3") (pintype "passive"))
    )
    (net (code "97") (name "PF3") (class "Default")
      (node (ref "U1") (pin "P$45") (pinfunction "PF3_P$45") (pintype "bidirectional"))
      (node (ref "X11") (pin "72") (pinfunction "1_72") (pintype "passive"))
      (node (ref "X9") (pin "5") (pinfunction "1_5") (pintype "passive"))
    )
    (net (code "98") (name "PF4") (class "Default")
      (node (ref "D3") (pin "A") (pinfunction "A_A") (pintype "passive"))
      (node (ref "U1") (pin "P$46") (pinfunction "PF4_P$46") (pintype "bidirectional"))
      (node (ref "X11") (pin "64") (pinfunction "1_64") (pintype "passive"))
    )
    (net (code "99") (name "PG0") (class "Default")
      (node (ref "U1") (pin "P$49") (pinfunction "PG0_P$49") (pintype "bidirectional"))
      (node (ref "X11") (pin "31") (pinfunction "1_31") (pintype "passive"))
      (node (ref "X9") (pin "7") (pinfunction "1_7") (pintype "passive"))
    )
    (net (code "100") (name "PG1") (class "Default")
      (node (ref "U1") (pin "P$50") (pinfunction "PG1_P$50") (pintype "bidirectional"))
      (node (ref "X11") (pin "29") (pinfunction "1_29") (pintype "passive"))
      (node (ref "X7") (pin "1") (pinfunction "1_1") (pintype "passive"))
    )
    (net (code "101") (name "PH0") (class "Default")
      (node (ref "U1") (pin "P$29") (pinfunction "PH0_P$29") (pintype "bidirectional"))
      (node (ref "X11") (pin "9") (pinfunction "1_9") (pintype "passive"))
      (node (ref "X7") (pin "13") (pinfunction "1_13") (pintype "passive"))
    )
    (net (code "102") (name "PH1") (class "Default")
      (node (ref "U1") (pin "P$30") (pinfunction "PH1_P$30") (pintype "bidirectional"))
      (node (ref "X11") (pin "11") (pinfunction "1_11") (pintype "passive"))
      (node (ref "X7") (pin "15") (pinfunction "1_15") (pintype "passive"))
    )
    (net (code "103") (name "PH2") (class "Default")
      (node (ref "U1") (pin "P$31") (pinfunction "PH2_P$31") (pintype "bidirectional"))
      (node (ref "X11") (pin "13") (pinfunction "1_13") (pintype "passive"))
      (node (ref "X9") (pin "6") (pinfunction "1_6") (pintype "passive"))
    )
    (net (code "104") (name "PH3") (class "Default")
      (node (ref "U1") (pin "P$32") (pinfunction "PH3_P$32") (pintype "bidirectional"))
      (node (ref "X11") (pin "15") (pinfunction "1_15") (pintype "passive"))
      (node (ref "X9") (pin "8") (pinfunction "1_8") (pintype "passive"))
    )
    (net (code "105") (name "PJ0") (class "Default")
      (node (ref "U1") (pin "P$116") (pinfunction "PJ0_P$116") (pintype "bidirectional"))
      (node (ref "USR_SW1") (pin "P$1") (pinfunction "0_P$1") (pintype "passive"))
      (node (ref "USR_SW1") (pin "P$2") (pinfunction "0_P$2") (pintype "passive"))
      (node (ref "X11") (pin "82") (pinfunction "1_82") (pintype "passive"))
    )
    (net (code "106") (name "PJ1") (class "Default")
      (node (ref "U1") (pin "P$117") (pinfunction "PJ1_P$117") (pintype "bidirectional"))
      (node (ref "USR_SW2") (pin "P$1") (pinfunction "0_P$1") (pintype "passive"))
      (node (ref "USR_SW2") (pin "P$2") (pinfunction "0_P$2") (pintype "passive"))
      (node (ref "X11") (pin "84") (pinfunction "1_84") (pintype "passive"))
    )
    (net (code "107") (name "PK0") (class "Default")
      (node (ref "U1") (pin "P$18") (pinfunction "PK0_P$18") (pintype "bidirectional"))
      (node (ref "X11") (pin "26") (pinfunction "1_26") (pintype "passive"))
      (node (ref "X6") (pin "10") (pinfunction "1_10") (pintype "passive"))
    )
    (net (code "108") (name "PK1") (class "Default")
      (node (ref "U1") (pin "P$19") (pinfunction "PK1_P$19") (pintype "bidirectional"))
      (node (ref "X11") (pin "28") (pinfunction "1_28") (pintype "passive"))
      (node (ref "X6") (pin "12") (pinfunction "1_12") (pintype "passive"))
    )
    (net (code "109") (name "PK2") (class "Default")
      (node (ref "U1") (pin "P$20") (pinfunction "PK2_P$20") (pintype "bidirectional"))
      (node (ref "X11") (pin "30") (pinfunction "1_30") (pintype "passive"))
      (node (ref "X6") (pin "14") (pinfunction "1_14") (pintype "passive"))
    )
    (net (code "110") (name "PK3") (class "Default")
      (node (ref "U1") (pin "P$21") (pinfunction "PK3_P$21") (pintype "bidirectional"))
      (node (ref "X11") (pin "32") (pinfunction "1_32") (pintype "passive"))
      (node (ref "X6") (pin "16") (pinfunction "1_16") (pintype "passive"))
    )
    (net (code "111") (name "PK4") (class "Default")
      (node (ref "U1") (pin "P$63") (pinfunction "PK4_P$63") (pintype "bidirectional"))
      (node (ref "X11") (pin "77") (pinfunction "1_77") (pintype "passive"))
      (node (ref "X7") (pin "3") (pinfunction "1_3") (pintype "passive"))
    )
    (net (code "112") (name "PK5") (class "Default")
      (node (ref "U1") (pin "P$62") (pinfunction "PK5_P$62") (pintype "bidirectional"))
      (node (ref "X11") (pin "75") (pinfunction "1_75") (pintype "passive"))
      (node (ref "X7") (pin "5") (pinfunction "1_5") (pintype "passive"))
    )
    (net (code "113") (name "PK6") (class "Default")
      (node (ref "U1") (pin "P$61") (pinfunction "PK6_P$61") (pintype "bidirectional"))
      (node (ref "X11") (pin "63") (pinfunction "1_63") (pintype "passive"))
      (node (ref "X7") (pin "17") (pinfunction "1_17") (pintype "passive"))
    )
    (net (code "114") (name "PK7") (class "Default")
      (node (ref "U1") (pin "P$60") (pinfunction "PK7_P$60") (pintype "bidirectional"))
      (node (ref "X11") (pin "59") (pinfunction "1_59") (pintype "passive"))
      (node (ref "X7") (pin "19") (pinfunction "1_19") (pintype "passive"))
    )
    (net (code "115") (name "PL0") (class "Default")
      (node (ref "U1") (pin "P$81") (pinfunction "PL0_P$81") (pintype "bidirectional"))
      (node (ref "X11") (pin "43") (pinfunction "1_43") (pintype "passive"))
      (node (ref "X9") (pin "13") (pinfunction "1_13") (pintype "passive"))
    )
    (net (code "116") (name "PL1") (class "Default")
      (node (ref "U1") (pin "P$82") (pinfunction "PL1_P$82") (pintype "bidirectional"))
      (node (ref "X11") (pin "45") (pinfunction "1_45") (pintype "passive"))
      (node (ref "X9") (pin "15") (pinfunction "1_15") (pintype "passive"))
    )
    (net (code "117") (name "PL2") (class "Default")
      (node (ref "U1") (pin "P$83") (pinfunction "PL2_P$83") (pintype "bidirectional"))
      (node (ref "X11") (pin "47") (pinfunction "1_47") (pintype "passive"))
      (node (ref "X9") (pin "17") (pinfunction "1_17") (pintype "passive"))
    )
    (net (code "118") (name "PL3") (class "Default")
      (node (ref "U1") (pin "P$84") (pinfunction "PL3_P$84") (pintype "bidirectional"))
      (node (ref "X11") (pin "49") (pinfunction "1_49") (pintype "passive"))
      (node (ref "X9") (pin "19") (pinfunction "1_19") (pintype "passive"))
    )
    (net (code "119") (name "PL4") (class "Default")
      (node (ref "U1") (pin "P$85") (pinfunction "PL4_P$85") (pintype "bidirectional"))
      (node (ref "X11") (pin "65") (pinfunction "1_65") (pintype "passive"))
      (node (ref "X9") (pin "9") (pinfunction "1_9") (pintype "passive"))
    )
    (net (code "120") (name "PL5") (class "Default")
      (node (ref "U1") (pin "P$86") (pinfunction "PL5_P$86") (pintype "bidirectional"))
      (node (ref "X11") (pin "79") (pinfunction "1_79") (pintype "passive"))
      (node (ref "X9") (pin "11") (pinfunction "1_11") (pintype "passive"))
    )
    (net (code "121") (name "PM0") (class "Default")
      (node (ref "U1") (pin "P$78") (pinfunction "PM0_P$78") (pintype "bidirectional"))
      (node (ref "X11") (pin "41") (pinfunction "1_41") (pintype "passive"))
      (node (ref "X7") (pin "7") (pinfunction "1_7") (pintype "passive"))
    )
    (net (code "122") (name "PM1") (class "Default")
      (node (ref "U1") (pin "P$77") (pinfunction "PM1_P$77") (pintype "bidirectional"))
      (node (ref "X11") (pin "39") (pinfunction "1_39") (pintype "passive"))
      (node (ref "X7") (pin "9") (pinfunction "1_9") (pintype "passive"))
    )
    (net (code "123") (name "PM2") (class "Default")
      (node (ref "U1") (pin "P$76") (pinfunction "PM2_P$76") (pintype "bidirectional"))
      (node (ref "X11") (pin "37") (pinfunction "1_37") (pintype "passive"))
      (node (ref "X7") (pin "11") (pinfunction "1_11") (pintype "passive"))
    )
    (net (code "124") (name "PM3") (class "Default")
      (node (ref "U1") (pin "P$75") (pinfunction "PM3_P$75") (pintype "bidirectional"))
      (node (ref "X11") (pin "33") (pinfunction "1_33") (pintype "passive"))
      (node (ref "X9") (pin "4") (pinfunction "1_4") (pintype "passive"))
    )
    (net (code "125") (name "PM4") (class "Default")
      (node (ref "U1") (pin "P$74") (pinfunction "PM4_P$74") (pintype "bidirectional"))
      (node (ref "X11") (pin "92") (pinfunction "1_92") (pintype "passive"))
      (node (ref "X8") (pin "18") (pinfunction "1_18") (pintype "passive"))
    )
    (net (code "126") (name "PM5") (class "Default")
      (node (ref "U1") (pin "P$73") (pinfunction "PM5_P$73") (pintype "bidirectional"))
      (node (ref "X11") (pin "90") (pinfunction "1_90") (pintype "passive"))
      (node (ref "X8") (pin "20") (pinfunction "1_20") (pintype "passive"))
    )
    (net (code "127") (name "PM6") (class "Default")
      (node (ref "U1") (pin "P$72") (pinfunction "PM6_P$72") (pintype "bidirectional"))
      (node (ref "X11") (pin "88") (pinfunction "1_88") (pintype "passive"))
      (node (ref "X7") (pin "20") (pinfunction "1_20") (pintype "passive"))
    )
    (net (code "128") (name "PM7") (class "Default")
      (node (ref "U1") (pin "P$71") (pinfunction "PM7_P$71") (pintype "bidirectional"))
      (node (ref "X11") (pin "86") (pinfunction "1_86") (pintype "passive"))
      (node (ref "X7") (pin "4") (pinfunction "1_4") (pintype "passive"))
    )
    (net (code "129") (name "PN0") (class "Default")
      (node (ref "D2") (pin "A") (pinfunction "A_A") (pintype "passive"))
      (node (ref "U1") (pin "P$107") (pinfunction "PN0_P$107") (pintype "bidirectional"))
      (node (ref "X11") (pin "85") (pinfunction "1_85") (pintype "passive"))
    )
    (net (code "130") (name "PN1") (class "Default")
      (node (ref "D1") (pin "A") (pinfunction "A_A") (pintype "passive"))
      (node (ref "U1") (pin "P$108") (pinfunction "PN1_P$108") (pintype "bidirectional"))
      (node (ref "X11") (pin "87") (pinfunction "1_87") (pintype "passive"))
    )
    (net (code "131") (name "PN2") (class "Default")
      (node (ref "U1") (pin "P$109") (pinfunction "PN2_P$109") (pintype "bidirectional"))
      (node (ref "X11") (pin "89") (pinfunction "1_89") (pintype "passive"))
      (node (ref "X9") (pin "16") (pinfunction "1_16") (pintype "passive"))
    )
    (net (code "132") (name "PN3") (class "Default")
      (node (ref "U1") (pin "P$110") (pinfunction "PN3_P$110") (pintype "bidirectional"))
      (node (ref "X11") (pin "91") (pinfunction "1_91") (pintype "passive"))
      (node (ref "X9") (pin "18") (pinfunction "1_18") (pintype "passive"))
    )
    (net (code "133") (name "PN4") (class "Default")
      (node (ref "U1") (pin "P$111") (pinfunction "PN4_P$111") (pintype "bidirectional"))
      (node (ref "X11") (pin "81") (pinfunction "1_81") (pintype "passive"))
      (node (ref "X6") (pin "19") (pinfunction "1_19") (pintype "passive"))
    )
    (net (code "134") (name "PN5") (class "Default")
      (node (ref "U1") (pin "P$112") (pinfunction "PN5_P$112") (pintype "bidirectional"))
      (node (ref "X11") (pin "83") (pinfunction "1_83") (pintype "passive"))
      (node (ref "X6") (pin "17") (pinfunction "1_17") (pintype "passive"))
    )
    (net (code "135") (name "PP0") (class "Default")
      (node (ref "U1") (pin "P$118") (pinfunction "PP0_P$118") (pintype "bidirectional"))
      (node (ref "X11") (pin "54") (pinfunction "1_54") (pintype "passive"))
      (node (ref "X6") (pin "5") (pinfunction "1_5") (pintype "passive"))
    )
    (net (code "136") (name "PP1") (class "Default")
      (node (ref "U1") (pin "P$119") (pinfunction "PP1_P$119") (pintype "bidirectional"))
      (node (ref "X11") (pin "56") (pinfunction "1_56") (pintype "passive"))
      (node (ref "X6") (pin "7") (pinfunction "1_7") (pintype "passive"))
    )
    (net (code "137") (name "PP2") (class "Default")
      (node (ref "U1") (pin "P$103") (pinfunction "PP2_P$103") (pintype "bidirectional"))
      (node (ref "X11") (pin "71") (pinfunction "1_71") (pintype "passive"))
      (node (ref "X9") (pin "20") (pinfunction "1_20") (pintype "passive"))
    )
    (net (code "138") (name "PP3") (class "Default")
      (node (ref "U1") (pin "P$104") (pinfunction "PP3_P$104") (pintype "bidirectional"))
      (node (ref "X11") (pin "73") (pinfunction "1_73") (pintype "passive"))
      (node (ref "X7") (pin "16") (pinfunction "1_16") (pintype "passive"))
    )
    (net (code "139") (name "PP4") (class "Default")
      (node (ref "U1") (pin "P$105") (pinfunction "PP4_P$105") (pintype "bidirectional"))
      (node (ref "X11") (pin "78") (pinfunction "1_78") (pintype "passive"))
      (node (ref "X6") (pin "15") (pinfunction "1_15") (pintype "passive"))
    )
    (net (code "140") (name "PP5") (class "Default")
      (node (ref "U1") (pin "P$106") (pinfunction "PP5_P$106") (pintype "bidirectional"))
      (node (ref "X11") (pin "80") (pinfunction "1_80") (pintype "passive"))
      (node (ref "X7") (pin "6") (pinfunction "1_6") (pintype "passive"))
    )
    (net (code "141") (name "PQ0") (class "Default")
      (node (ref "U1") (pin "P$5") (pinfunction "PQ0_P$5") (pintype "bidirectional"))
      (node (ref "X11") (pin "51") (pinfunction "1_51") (pintype "passive"))
      (node (ref "X6") (pin "13") (pinfunction "1_13") (pintype "passive"))
    )
    (net (code "142") (name "PQ1") (class "Default")
      (node (ref "U1") (pin "P$6") (pinfunction "PQ1_P$6") (pintype "bidirectional"))
      (node (ref "X11") (pin "53") (pinfunction "1_53") (pintype "passive"))
      (node (ref "X7") (pin "18") (pinfunction "1_18") (pintype "passive"))
    )
    (net (code "143") (name "PQ2") (class "Default")
      (node (ref "R19") (pin "1") (pinfunction "1_1") (pintype "passive"))
      (node (ref "U1") (pin "P$11") (pinfunction "PQ2_P$11") (pintype "bidirectional"))
      (node (ref "X11") (pin "55") (pinfunction "1_55") (pintype "passive"))
      (node (ref "X7") (pin "12") (pinfunction "1_12") (pintype "passive"))
    )
    (net (code "144") (name "PQ3") (class "Default")
      (node (ref "R20") (pin "1") (pinfunction "1_1") (pintype "passive"))
      (node (ref "U1") (pin "P$27") (pinfunction "PQ3_P$27") (pintype "bidirectional"))
      (node (ref "X11") (pin "57") (pinfunction "1_57") (pintype "passive"))
      (node (ref "X7") (pin "14") (pinfunction "1_14") (pintype "passive"))
    )
    (net (code "145") (name "PQ4") (class "Default")
      (node (ref "U1") (pin "P$102") (pinfunction "PQ4_P$102") (pintype "bidirectional"))
      (node (ref "U4") (pin "5") (pinfunction "*OC2_5") (pintype "output"))
      (node (ref "X11") (pin "93") (pinfunction "1_93") (pintype "passive"))
    )
    (net (code "146") (name "RBIAS") (class "Default")
      (node (ref "R25") (pin "1") (pinfunction "1_1") (pintype "passive"))
      (node (ref "U1") (pin "P$59") (pinfunction "RBIAS_P$59") (pintype "bidirectional"))
    )
    (net (code "147") (name "TARGET_ID") (class "Default")
      (node (ref "R18") (pin "2") (pinfunction "2_2") (pintype "passive"))
      (node (ref "TP7") (pin "TP") (pinfunction "TP_TP") (pintype "input"))
      (node (ref "U2") (pin "2") (pinfunction "D-_2") (pintype "passive"))
      (node (ref "U7") (pin "P4") (pinfunction "ID_P4") (pintype "bidirectional"))
    )
    (net (code "148") (name "TARGET_RXD") (class "Default")
      (node (ref "JP4") (pin "1") (pinfunction "1_1") (pintype "passive"))
      (node (ref "R7") (pin "1") (pinfunction "1_1") (pintype "passive"))
      (node (ref "X1") (pin "12") (pinfunction "1_12") (pintype "passive"))
    )
    (net (code "149") (name "TARGET_TCK{slash}SWCLK") (class "Default")
      (node (ref "R1") (pin "2") (pinfunction "2_2") (pintype "passive"))
      (node (ref "R8") (pin "1") (pinfunction "1_1") (pintype "passive"))
      (node (ref "U1") (pin "P$100") (pinfunction "PC0_P$100") (pintype "bidirectional"))
      (node (ref "X1") (pin "10") (pinfunction "1_10") (pintype "passive"))
    )
    (net (code "150") (name "TARGET_TDI") (class "Default")
      (node (ref "R11") (pin "1") (pinfunction "1_1") (pintype "passive"))
      (node (ref "U1") (pin "P$98") (pinfunction "PC2_P$98") (pintype "bidirectional"))
      (node (ref "X1") (pin "6") (pinfunction "1_6") (pintype "passive"))
    )
    (net (code "151") (name "TARGET_TDO{slash}SWO") (class "Default")
      (node (ref "R15") (pin "1") (pinfunction "1_1") (pintype "passive"))
      (node (ref "U1") (pin "P$97") (pinfunction "PC3_P$97") (pintype "bidirectional"))
      (node (ref "X1") (pin "4") (pinfunction "1_4") (pintype "passive"))
    )
    (net (code "152") (name "TARGET_TMS{slash}SWDIO") (class "Default")
      (node (ref "R10") (pin "1") (pinfunction "1_1") (pintype "passive"))
      (node (ref "R2") (pin "2") (pinfunction "2_2") (pintype "passive"))
      (node (ref "U1") (pin "P$99") (pinfunction "PC1_P$99") (pintype "bidirectional"))
      (node (ref "X1") (pin "8") (pinfunction "1_8") (pintype "passive"))
    )
    (net (code "153") (name "TARGET_TXD") (class "Default")
      (node (ref "JP5") (pin "1") (pinfunction "1_1") (pintype "passive"))
      (node (ref "R6") (pin "1") (pinfunction "1_1") (pintype "passive"))
      (node (ref "X1") (pin "14") (pinfunction "1_14") (pintype "passive"))
    )
    (net (code "154") (name "TARGET_VBUS") (class "Default")
      (node (ref "JP1") (pin "3") (pinfunction "3_3") (pintype "passive"))
      (node (ref "TP4") (pin "TP") (pinfunction "TP_TP") (pintype "input"))
      (node (ref "U1") (pin "P$96") (pinfunction "PB1_P$96") (pintype "bidirectional"))
      (node (ref "U2") (pin "6") (pinfunction "VBUS_6") (pintype "passive"))
      (node (ref "U4") (pin "6") (pinfunction "OUT2_6") (pintype "output"))
      (node (ref "U7") (pin "P1") (pinfunction "VBUS_P1") (pintype "bidirectional"))
      (node (ref "X11") (pin "60") (pinfunction "1_60") (pintype "passive"))
    )
    (net (code "155") (name "USBD_N") (class "Default")
      (node (ref "TP5") (pin "TP") (pinfunction "TP_TP") (pintype "input"))
      (node (ref "U1") (pin "P$93") (pinfunction "PL7_P$93") (pintype "bidirectional"))
      (node (ref "U2") (pin "1") (pinfunction "D+_1") (pintype "passive"))
      (node (ref "U7") (pin "P2") (pinfunction "DM_P2") (pintype "bidirectional"))
    )
    (net (code "156") (name "USBD_P") (class "Default")
      (node (ref "TP6") (pin "TP") (pinfunction "TP_TP") (pintype "input"))
      (node (ref "U1") (pin "P$94") (pinfunction "PL6_P$94") (pintype "bidirectional"))
      (node (ref "U2") (pin "3") (pinfunction "ID_3") (pintype "passive"))
      (node (ref "U7") (pin "P3") (pinfunction "DP_P3") (pintype "bidirectional"))
    )
    (net (code "157") (name "VBUS") (class "Default")
      (node (ref "JP1") (pin "2") (pinfunction "2_2") (pintype "passive"))
      (node (ref "JP1") (pin "4") (pinfunction "4_4") (pintype "passive"))
      (node (ref "JP1") (pin "6") (pinfunction "6_6") (pintype "passive"))
      (node (ref "R35") (pin "1") (pinfunction "1_1") (pintype "passive"))
      (node (ref "R36") (pin "2") (pinfunction "2_2") (pintype "passive"))
      (node (ref "U4") (pin "2") (pinfunction "IN_2") (pintype "input"))
    )
    (net (code "158") (name "VCP_RXD") (class "Default")
      (node (ref "R6") (pin "2") (pinfunction "2_2") (pintype "passive"))
      (node (ref "U20") (pin "P$17") (pinfunction "PA0_P$17") (pintype "bidirectional"))
      (node (ref "X1") (pin "13") (pinfunction "1_13") (pintype "passive"))
    )
    (net (code "159") (name "VCP_TXD") (class "Default")
      (node (ref "R7") (pin "2") (pinfunction "2_2") (pintype "passive"))
      (node (ref "U20") (pin "P$18") (pinfunction "PA1_P$18") (pintype "bidirectional"))
      (node (ref "X1") (pin "11") (pinfunction "1_11") (pintype "passive"))
    )
    (net (code "160") (name "VERSION_0") (class "Default")
      (node (ref "R12") (pin "1") (pinfunction "1_1") (pintype "passive"))
      (node (ref "U20") (pin "P$61") (pinfunction "PD0_P$61") (pintype "bidirectional"))
    )
    (net (code "161") (name "VERSION_1") (class "Default")
      (node (ref "R13") (pin "1") (pinfunction "1_1") (pintype "passive"))
      (node (ref "U20") (pin "P$47") (pinfunction "PB2_P$47") (pintype "bidirectional"))
    )
    (net (code "162") (name "VERSION_2") (class "Default")
      (node (ref "R14") (pin "1") (pinfunction "1_1") (pintype "passive"))
      (node (ref "U20") (pin "P$48") (pinfunction "PB3_P$48") (pintype "bidirectional"))
    )
    (net (code "163") (name "VREF+") (class "Default")
      (node (ref "R41") (pin "1") (pinfunction "1_1") (pintype "passive"))
      (node (ref "TP13") (pin "TP") (pinfunction "TP_TP") (pintype "input"))
      (node (ref "U1") (pin "P$9") (pinfunction "VREFA+_P$9") (pintype "bidirectional"))
      (node (ref "X11") (pin "34") (pinfunction "1_34") (pintype "passive"))
    )
    (net (code "164") (name "unconnected-(JP1-Pad1)") (class "Default")
      (node (ref "JP1") (pin "1") (pinfunction "1_1") (pintype "passive"))
    )
    (net (code "165") (name "unconnected-(U2-N.C.-Pad5)") (class "Default")
      (node (ref "U2") (pin "5") (pinfunction "N.C._5") (pintype "no_connect"))
    )
    (net (code "166") (name "unconnected-(U3-ID-Pad3)") (class "Default")
      (node (ref "U3") (pin "3") (pinfunction "ID_3") (pintype "passive"))
    )
    (net (code "167") (name "unconnected-(U3-N.C.-Pad5)") (class "Default")
      (node (ref "U3") (pin "5") (pinfunction "N.C._5") (pintype "no_connect"))
    )
    (net (code "168") (name "unconnected-(U5-NC-Pad5)") (class "Default")
      (node (ref "U5") (pin "5") (pinfunction "NC_5") (pintype "passive"))
    )
    (net (code "169") (name "unconnected-(U6-P$7-PadP7)") (class "Default")
      (node (ref "U6") (pin "P7") (pinfunction "P$7_P7") (pintype "bidirectional"))
    )
    (net (code "170") (name "unconnected-(U20-PB0-PadP$45)") (class "Default")
      (node (ref "U20") (pin "P$45") (pinfunction "PB0_P$45") (pintype "bidirectional"))
    )
    (net (code "171") (name "unconnected-(U20-PB4-PadP$58)") (class "Default")
      (node (ref "U20") (pin "P$58") (pinfunction "PB4_P$58") (pintype "bidirectional"))
    )
    (net (code "172") (name "unconnected-(U20-PB5-PadP$57)") (class "Default")
      (node (ref "U20") (pin "P$57") (pinfunction "PB5_P$57") (pintype "bidirectional"))
    )
    (net (code "173") (name "unconnected-(U20-PB6-PadP$1)") (class "Default")
      (node (ref "U20") (pin "P$1") (pinfunction "PB6_P$1") (pintype "bidirectional"))
    )
    (net (code "174") (name "unconnected-(U20-PB7-PadP$4)") (class "Default")
      (node (ref "U20") (pin "P$4") (pinfunction "PB7_P$4") (pintype "bidirectional"))
    )
    (net (code "175") (name "unconnected-(U20-PC4-PadP$16)") (class "Default")
      (node (ref "U20") (pin "P$16") (pinfunction "PC4_P$16") (pintype "bidirectional"))
    )
    (net (code "176") (name "unconnected-(U20-PC5-PadP$15)") (class "Default")
      (node (ref "U20") (pin "P$15") (pinfunction "PC5_P$15") (pintype "bidirectional"))
    )
    (net (code "177") (name "unconnected-(U20-PC6-PadP$14)") (class "Default")
      (node (ref "U20") (pin "P$14") (pinfunction "PC6_P$14") (pintype "bidirectional"))
    )
    (net (code "178") (name "unconnected-(U20-PC7-PadP$13)") (class "Default")
      (node (ref "U20") (pin "P$13") (pinfunction "PC7_P$13") (pintype "bidirectional"))
    )
    (net (code "179") (name "unconnected-(U20-PD1-PadP$62)") (class "Default")
      (node (ref "U20") (pin "P$62") (pinfunction "PD1_P$62") (pintype "bidirectional"))
    )
    (net (code "180") (name "unconnected-(U20-PD2-PadP$63)") (class "Default")
      (node (ref "U20") (pin "P$63") (pinfunction "PD2_P$63") (pintype "bidirectional"))
    )
    (net (code "181") (name "unconnected-(U20-PD7-PadP$10)") (class "Default")
      (node (ref "U20") (pin "P$10") (pinfunction "PD7_P$10") (pintype "bidirectional"))
    )
    (net (code "182") (name "unconnected-(U20-PE0-PadP$9)") (class "Default")
      (node (ref "U20") (pin "P$9") (pinfunction "PE0_P$9") (pintype "bidirectional"))
    )
    (net (code "183") (name "unconnected-(U20-PE1-PadP$8)") (class "Default")
      (node (ref "U20") (pin "P$8") (pinfunction "PE1_P$8") (pintype "bidirectional"))
    )
    (net (code "184") (name "unconnected-(U20-PE2-PadP$7)") (class "Default")
      (node (ref "U20") (pin "P$7") (pinfunction "PE2_P$7") (pintype "bidirectional"))
    )
    (net (code "185") (name "unconnected-(U20-PE3-PadP$6)") (class "Default")
      (node (ref "U20") (pin "P$6") (pinfunction "PE3_P$6") (pintype "bidirectional"))
    )
    (net (code "186") (name "unconnected-(U20-PE4-PadP$59)") (class "Default")
      (node (ref "U20") (pin "P$59") (pinfunction "PE4_P$59") (pintype "bidirectional"))
    )
    (net (code "187") (name "unconnected-(U20-PE5-PadP$60)") (class "Default")
      (node (ref "U20") (pin "P$60") (pinfunction "PE5_P$60") (pintype "bidirectional"))
    )
    (net (code "188") (name "unconnected-(U20-PF0-PadP$28)") (class "Default")
      (node (ref "U20") (pin "P$28") (pinfunction "PF0_P$28") (pintype "bidirectional"))
    )
    (net (code "189") (name "unconnected-(U20-PF3-PadP$31)") (class "Default")
      (node (ref "U20") (pin "P$31") (pinfunction "PF3_P$31") (pintype "bidirectional"))
    )
    (net (code "190") (name "unconnected-(U20-PF4-PadP$5)") (class "Default")
      (node (ref "U20") (pin "P$5") (pinfunction "PF4_P$5") (pintype "bidirectional"))
    )
    (net (code "191") (name "unconnected-(U20-XOSC1-PadP$36)") (class "Default")
      (node (ref "U20") (pin "P$36") (pinfunction "XOSC1_P$36") (pintype "bidirectional"))
    )
    (net (code "192") (name "unconnected-(U20-~{HIB}-PadP$33)") (class "Default")
      (node (ref "U20") (pin "P$33") (pinfunction "~{HIB}_P$33") (pintype "bidirectional"))
    )
    (net (code "193") (name "unconnected-(U21-RTCK-Pad7)") (class "Default")
      (node (ref "U21") (pin "7") (pinfunction "RTCK_7") (pintype "bidirectional"))
    )
    (net (code "194") (name "unconnected-(U22A-ID-PadP4)") (class "Default")
      (node (ref "U22") (pin "P4") (pinfunction "ID_P4") (pintype "bidirectional"))
    )
    (net (code "195") (name "unconnected-(Y1-NC2-PadP$2)") (class "Default")
      (node (ref "Y1") (pin "P$2") (pinfunction "NC2_P$2") (pintype "bidirectional"))
    )
    (net (code "196") (name "unconnected-(Y1-NC4-PadP$4)") (class "Default")
      (node (ref "Y1") (pin "P$4") (pinfunction "NC4_P$4") (pintype "bidirectional"))
    )
    (net (code "197") (name "unconnected-(Y2-NC2-PadP$2)") (class "Default")
      (node (ref "Y2") (pin "P$2") (pinfunction "NC2_P$2") (pintype "bidirectional"))
    )
    (net (code "198") (name "unconnected-(Y2-NC4-PadP$4)") (class "Default")
      (node (ref "Y2") (pin "P$4") (pinfunction "NC4_P$4") (pintype "bidirectional"))
    )
    (net (code "199") (name "~{DEBUG_RESET_OUT}") (class "Default")
      (node (ref "R16") (pin "2") (pinfunction "2_2") (pintype "passive"))
      (node (ref "U20") (pin "P$23") (pinfunction "PA6_P$23") (pintype "bidirectional"))
      (node (ref "U6") (pin "P10") (pinfunction "~{RESET}_P10") (pintype "bidirectional"))
      (node (ref "X1") (pin "1") (pinfunction "1_1") (pintype "passive"))
    )
    (net (code "200") (name "~{EXTERNAL_DEBUG}") (class "Default")
      (node (ref "R40") (pin "1") (pinfunction "1_1") (pintype "passive"))
      (node (ref "TP2") (pin "TP") (pinfunction "TP_TP") (pintype "input"))
      (node (ref "U20") (pin "P$24") (pinfunction "PA7_P$24") (pintype "bidirectional"))
    )
    (net (code "201") (name "~{TARGET_RESET}") (class "Default")
      (node (ref "R16") (pin "1") (pinfunction "1_1") (pintype "passive"))
      (node (ref "R51") (pin "1") (pinfunction "1_1") (pintype "passive"))
      (node (ref "RESET") (pin "P$3") (pinfunction "1_P$3") (pintype "passive"))
      (node (ref "RESET") (pin "P$4") (pinfunction "1_P$4") (pintype "passive"))
      (node (ref "X1") (pin "2") (pinfunction "1_2") (pintype "passive"))
      (node (ref "X11") (pin "94") (pinfunction "1_94") (pintype "passive"))
      (node (ref "X7") (pin "10") (pinfunction "1_10") (pintype "passive"))
      (node (ref "X9") (pin "10") (pinfunction "1_10") (pintype "passive"))
    )
    (net (code "202") (name "~{WAKE}") (class "Default")
      (node (ref "R42") (pin "2") (pinfunction "2_2") (pintype "passive"))
      (node (ref "TP10") (pin "TP") (pinfunction "TP_TP") (pintype "input"))
      (node (ref "U1") (pin "P$64") (pinfunction "~{WAKE}_P$64") (pintype "bidirectional"))
      (node (ref "WAKE") (pin "P$1") (pinfunction "0_P$1") (pintype "passive"))
      (node (ref "WAKE") (pin "P$2") (pinfunction "0_P$2") (pintype "passive"))
      (node (ref "X11") (pin "95") (pinfunction "1_95") (pintype "passive"))
    )
  )
)
